# lippa.net
KiCad netlist of a schematic drawn in EAGLE
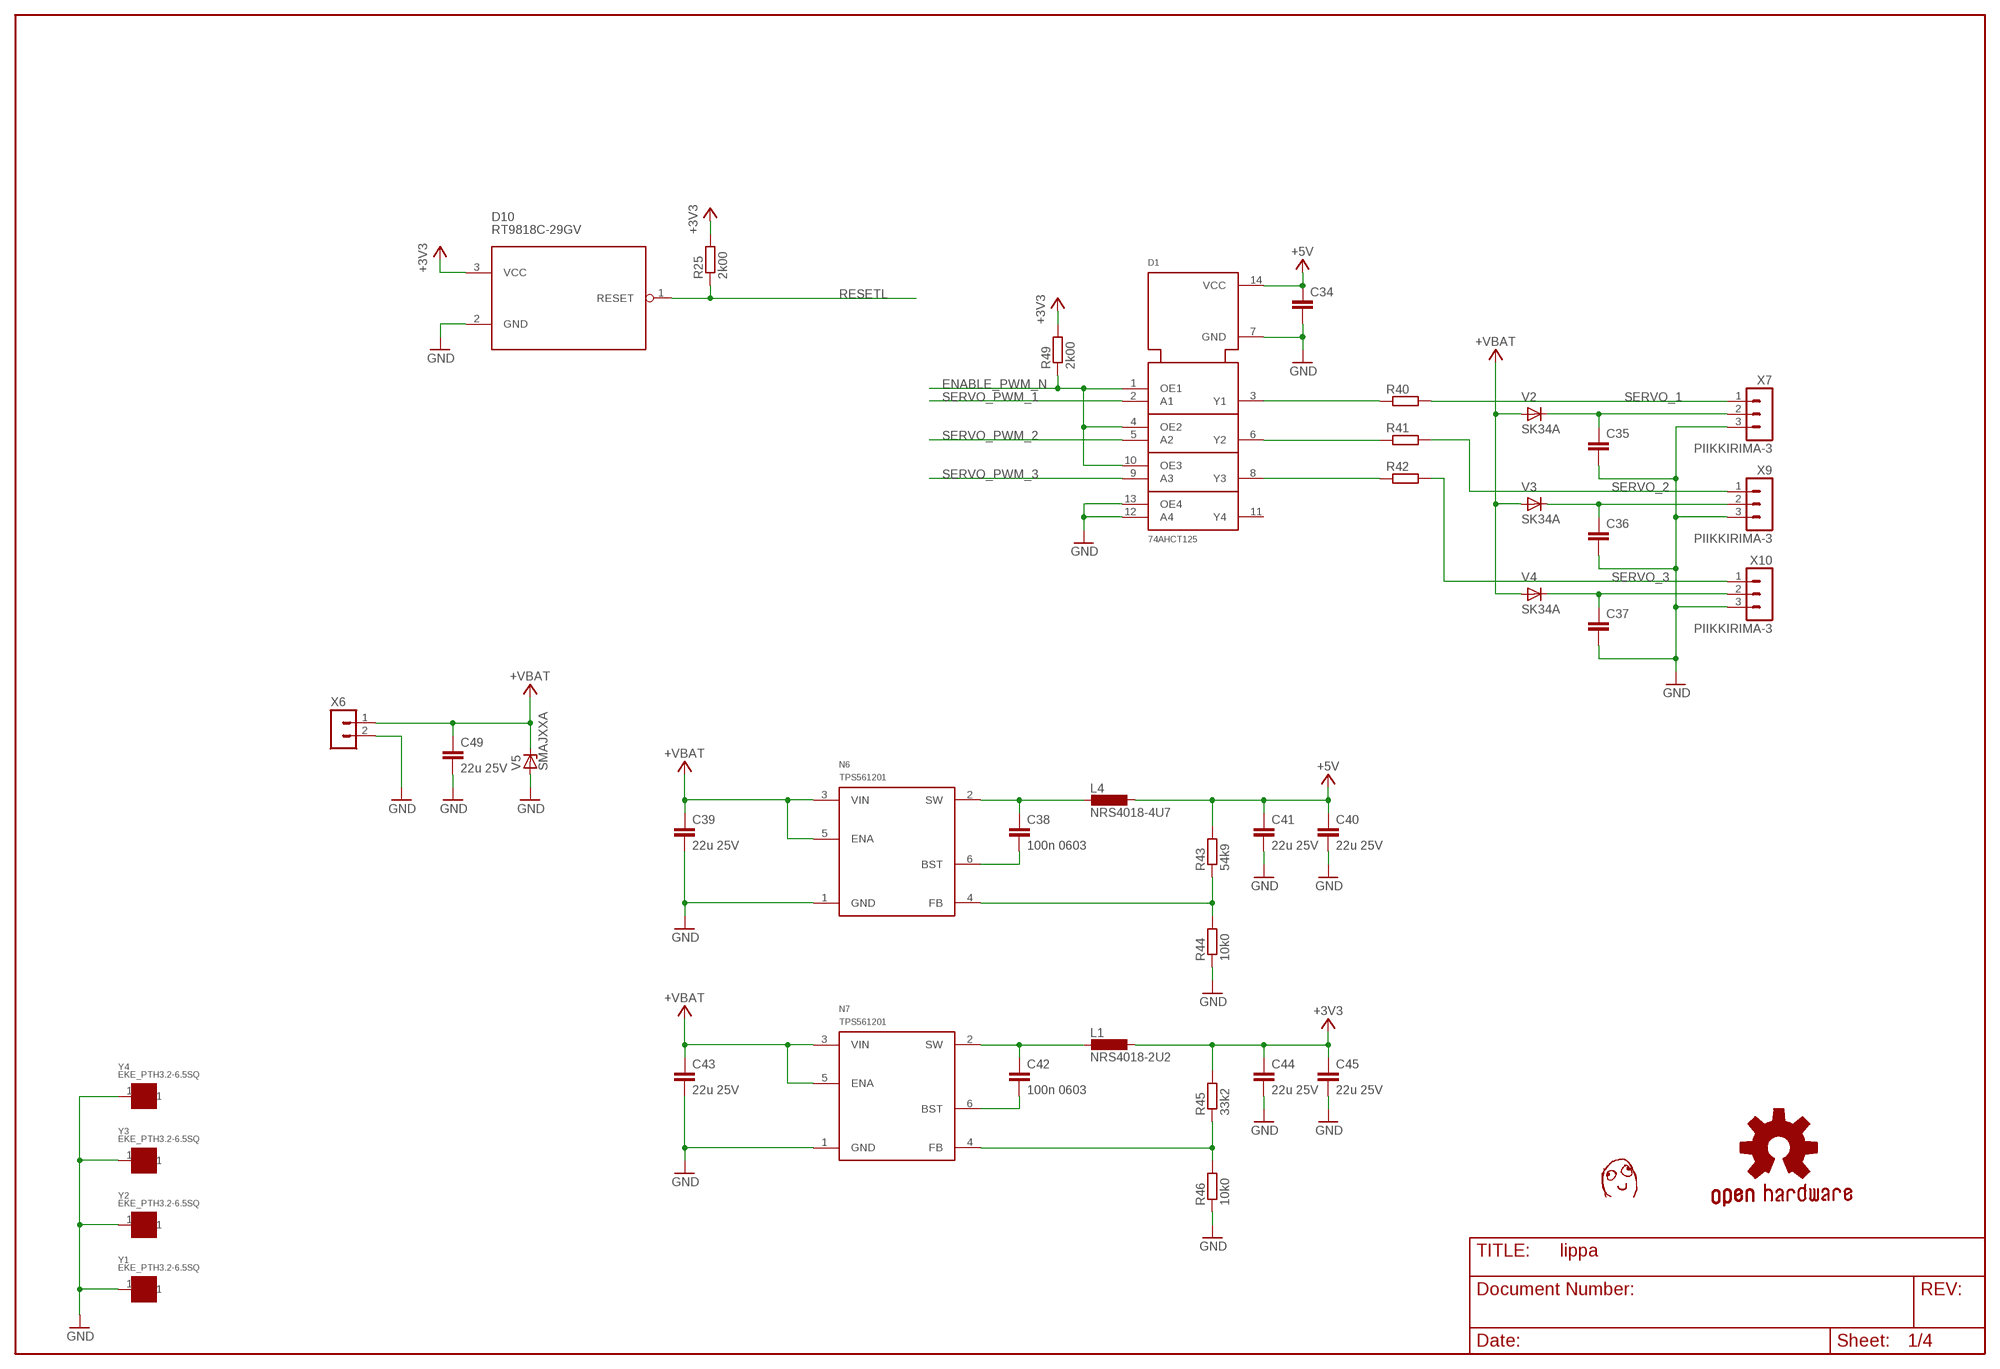
[diagram p0: schematic, sheet 1]
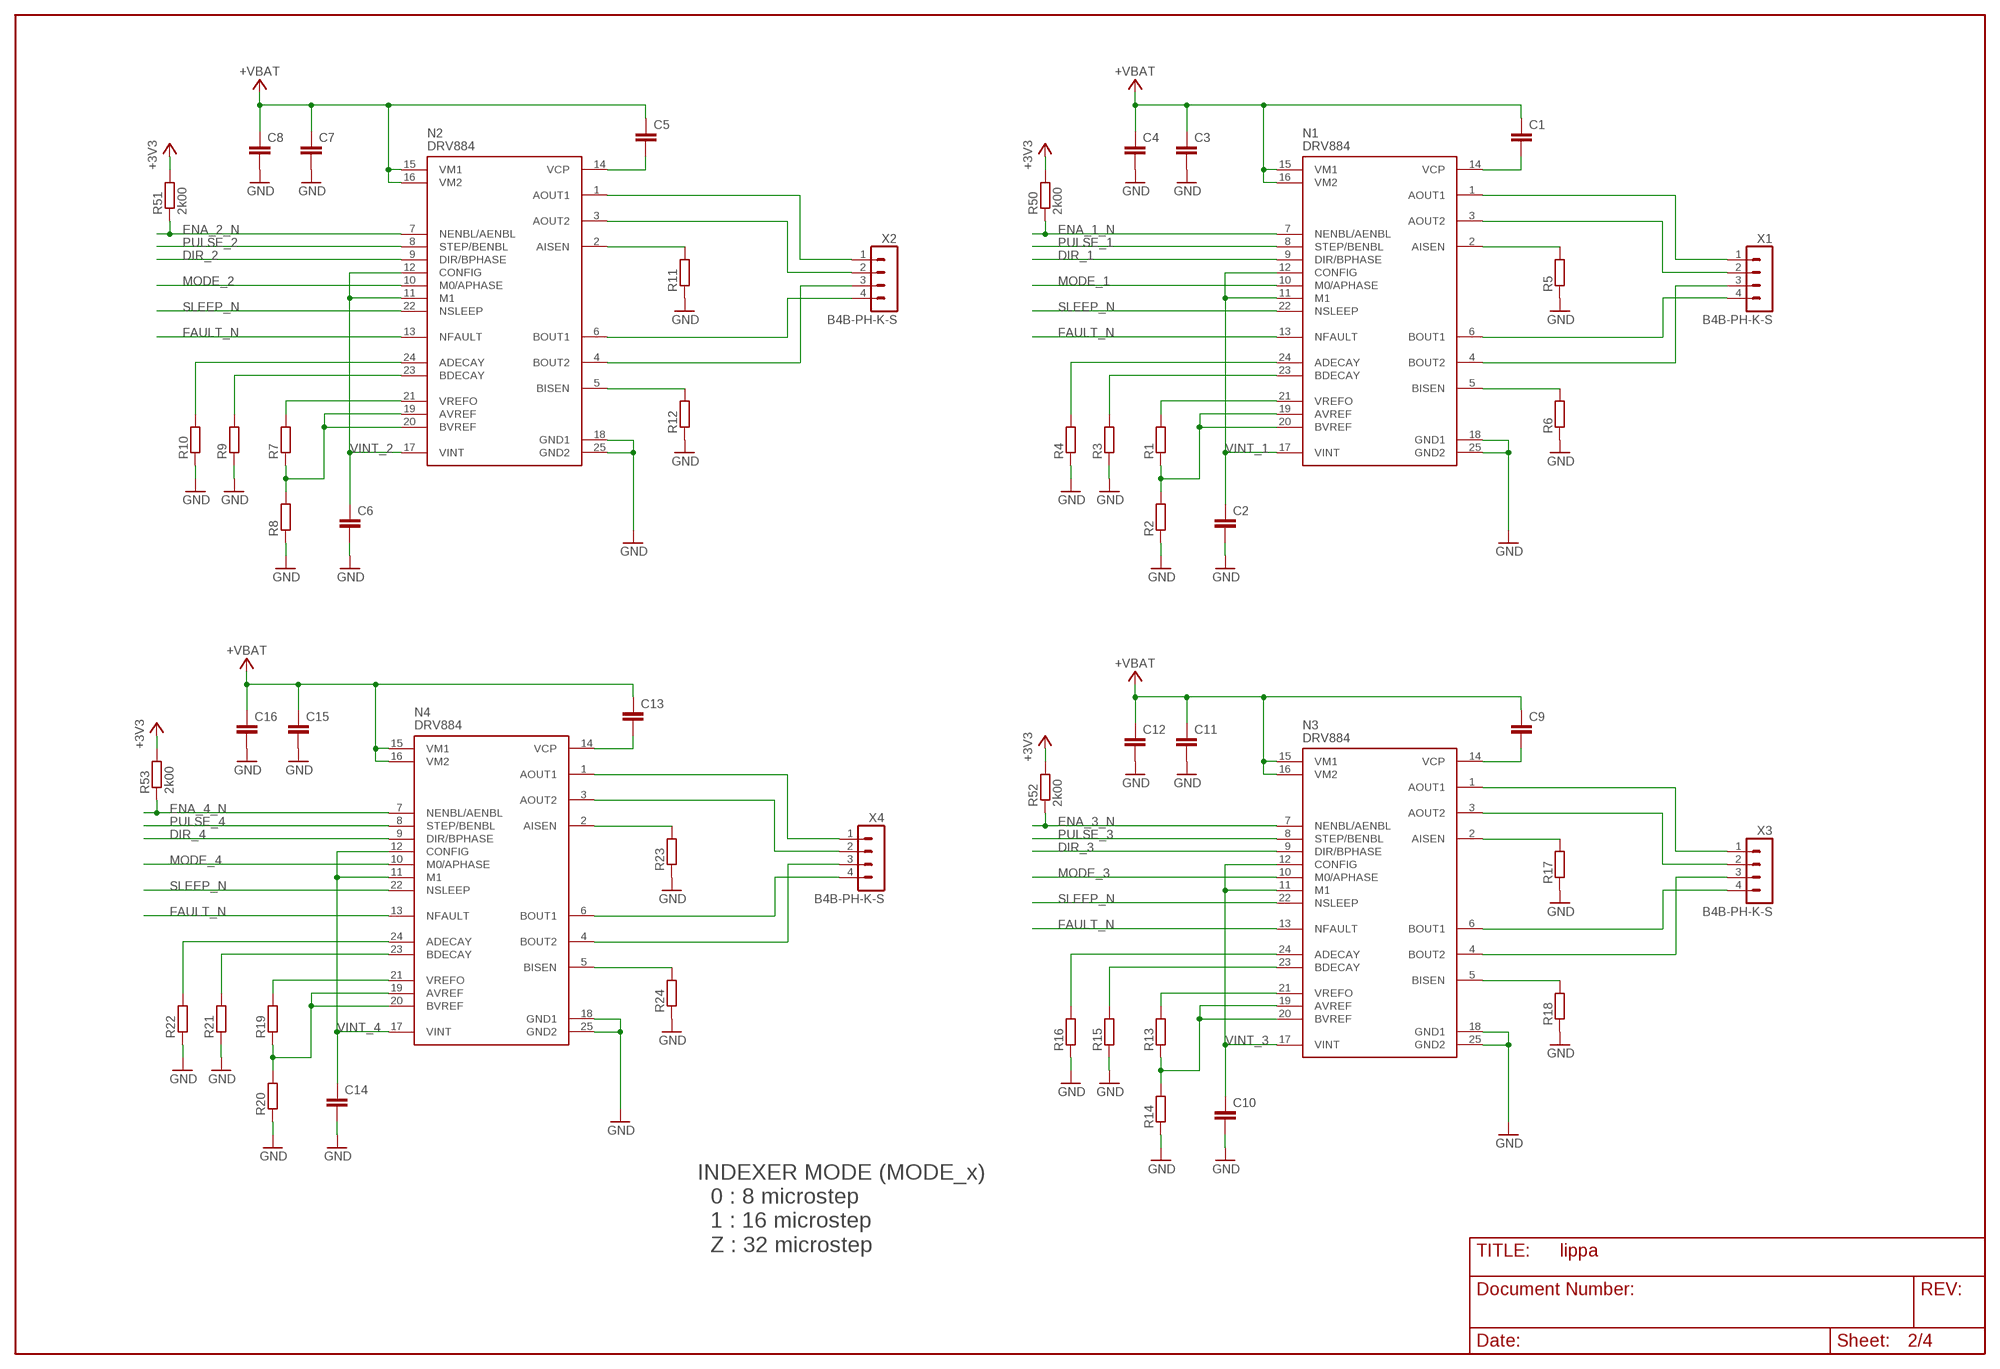
[diagram p1: schematic, sheet 2]
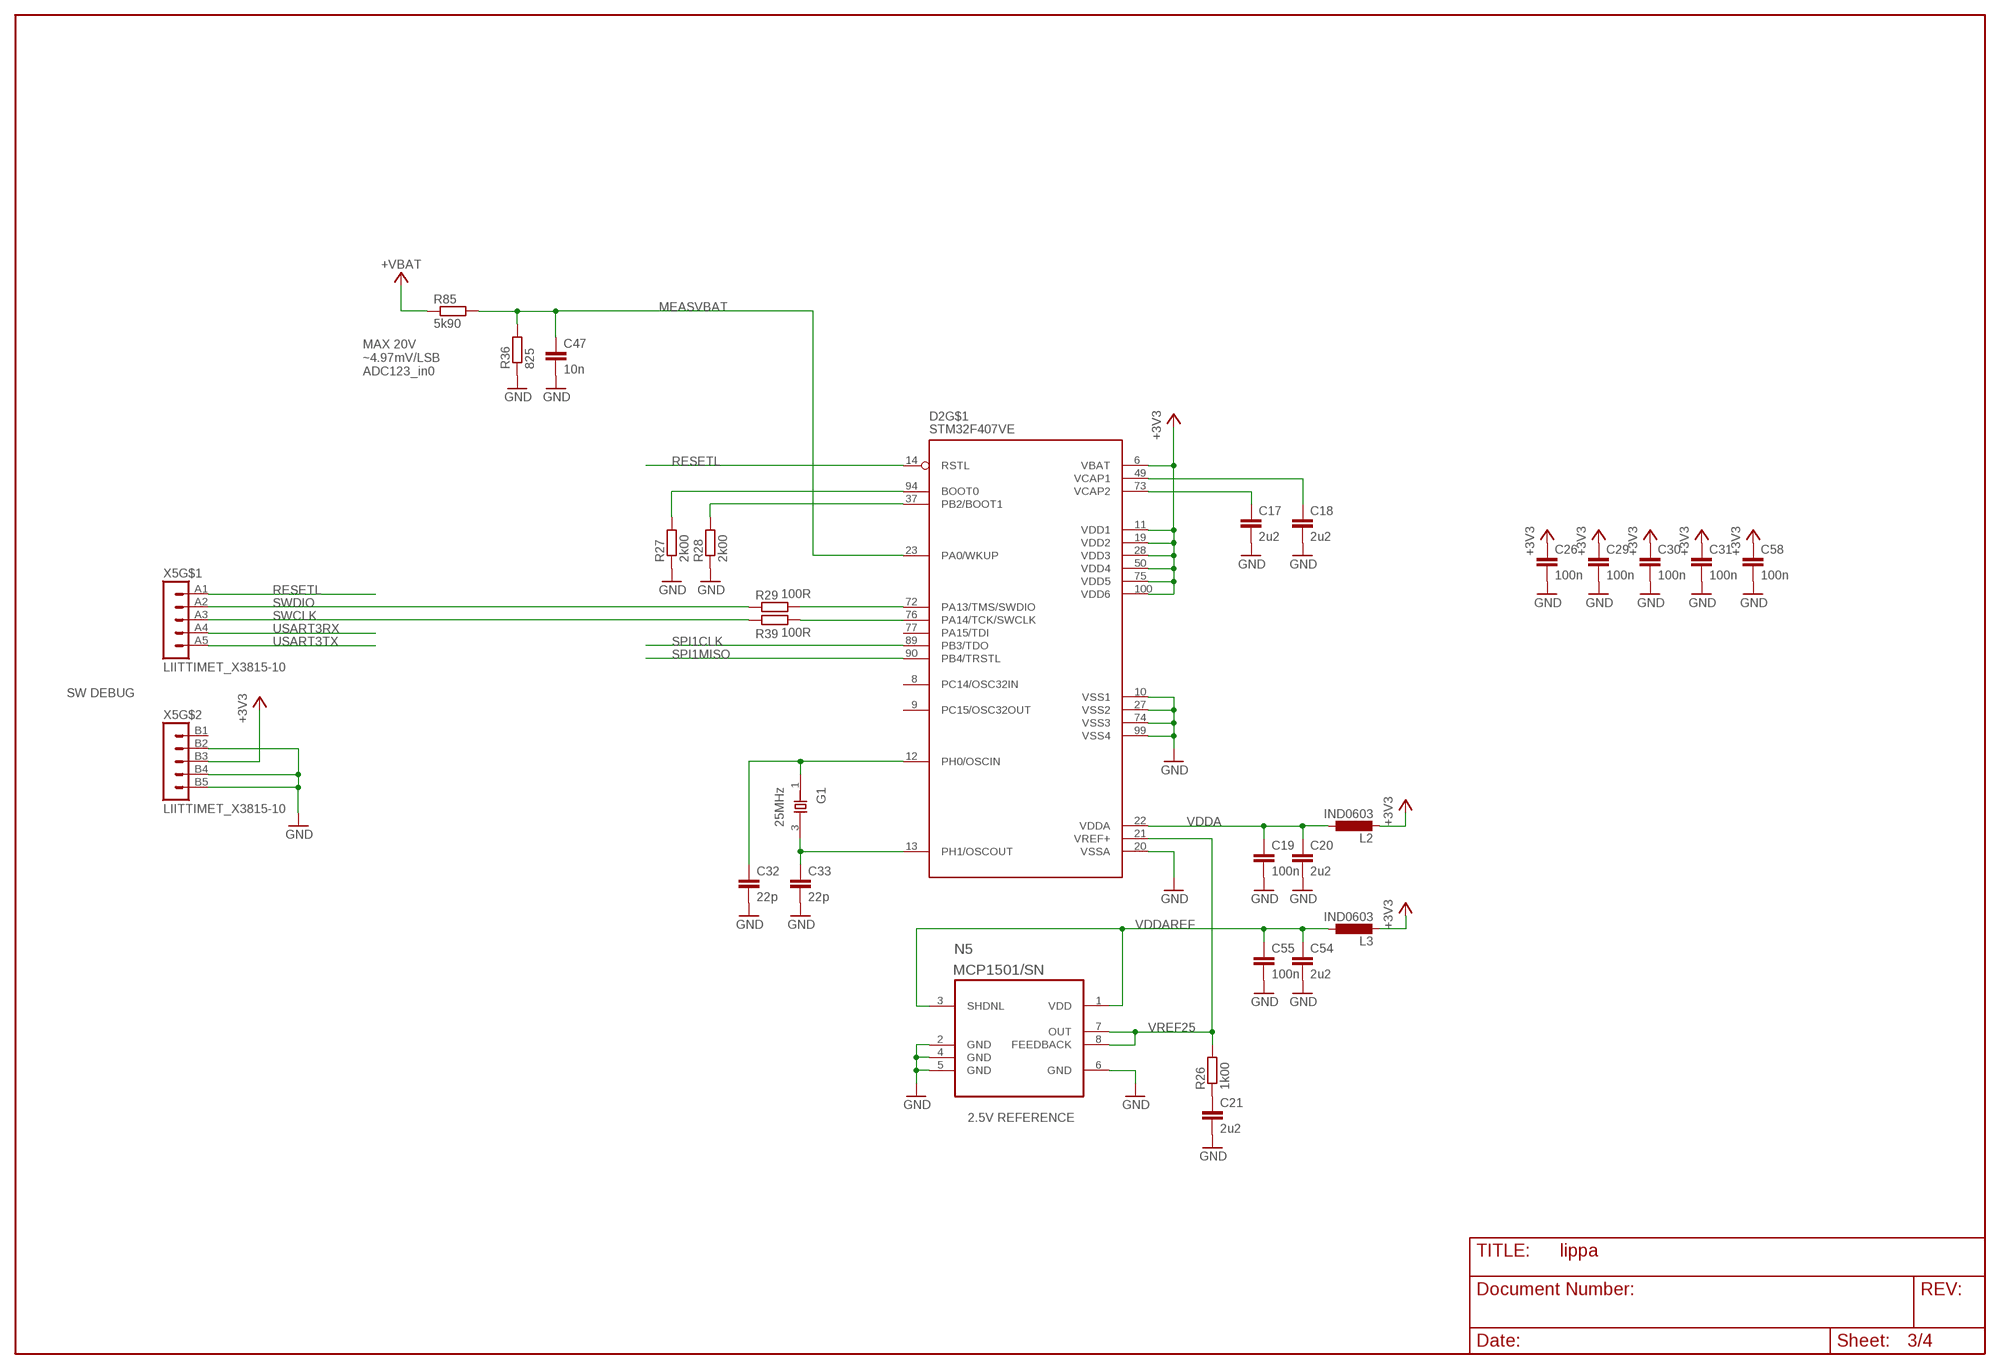
[diagram p2: schematic, sheet 3]
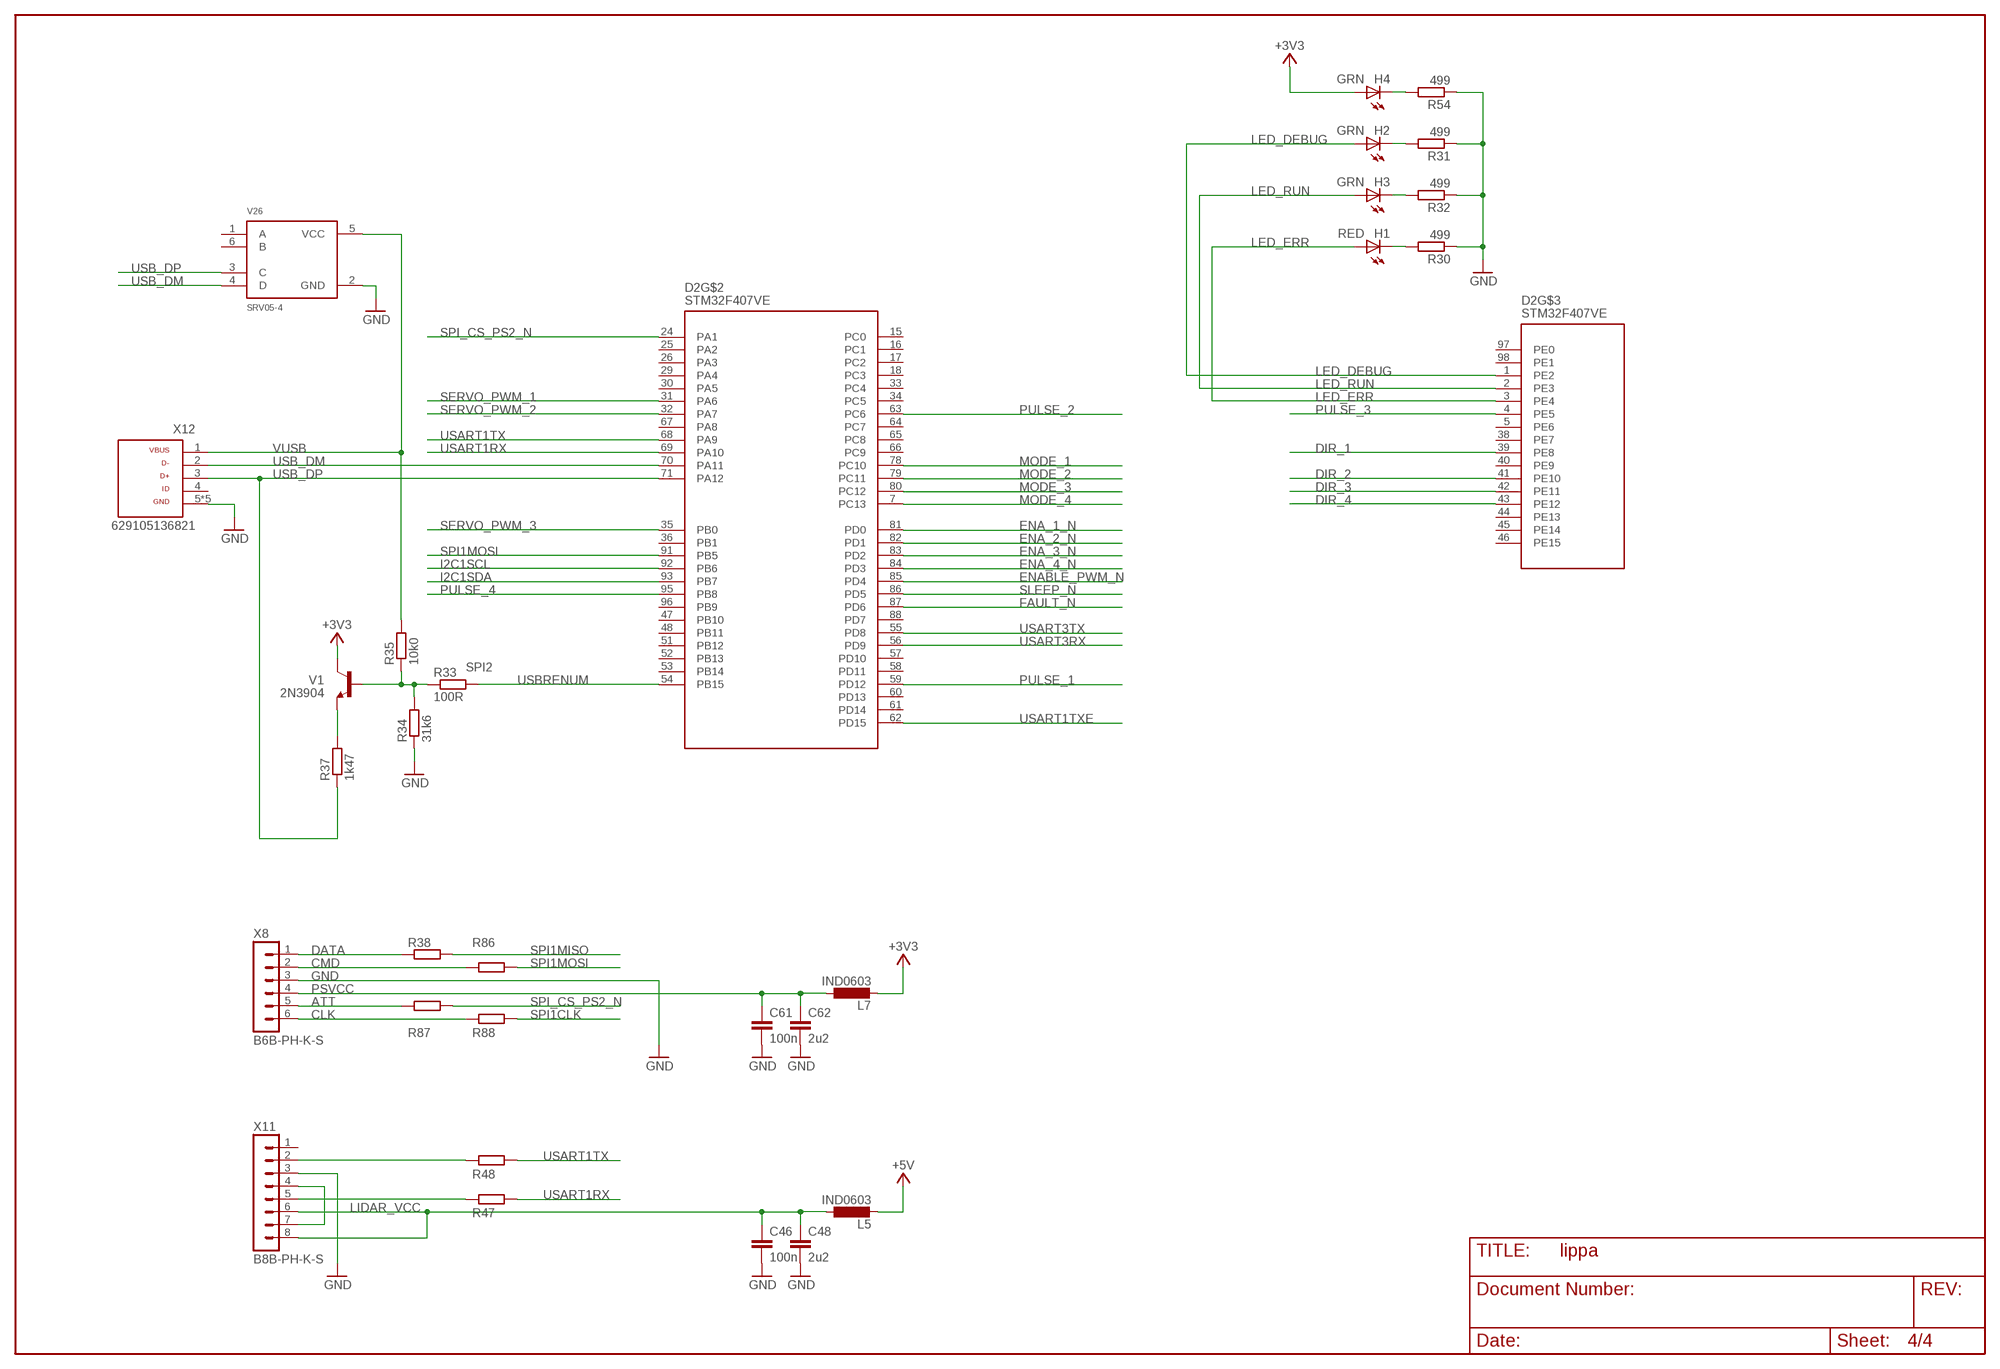
[diagram p3: schematic, sheet 4]

(export (version "E")
  (design (tool "Eeschema 10.0.6"))
  (components
    (comp (ref "C1")
      (value "OMAT_IC_2_CAP0603")
      (footprint "eagle-import:OMAT_IC_2_C0603")
      (libsource (lib "eagle-import") (part "OMAT_IC_2_CAP0603"))
    )
    (comp (ref "C2")
      (value "OMAT_IC_2_CAP0603")
      (footprint "eagle-import:OMAT_IC_2_C0603")
      (libsource (lib "eagle-import") (part "OMAT_IC_2_CAP0603"))
    )
    (comp (ref "C3")
      (value "OMAT_IC_2_CAP0603")
      (footprint "eagle-import:OMAT_IC_2_C0603")
      (libsource (lib "eagle-import") (part "OMAT_IC_2_CAP0603"))
    )
    (comp (ref "C4")
      (value "OMAT_IC_2_CAP0805")
      (footprint "eagle-import:OMAT_IC_2_C0805")
      (libsource (lib "eagle-import") (part "OMAT_IC_2_CAP0805"))
    )
    (comp (ref "C5")
      (value "OMAT_IC_2_CAP0603")
      (footprint "eagle-import:OMAT_IC_2_C0603")
      (libsource (lib "eagle-import") (part "OMAT_IC_2_CAP0603"))
    )
    (comp (ref "C6")
      (value "OMAT_IC_2_CAP0603")
      (footprint "eagle-import:OMAT_IC_2_C0603")
      (libsource (lib "eagle-import") (part "OMAT_IC_2_CAP0603"))
    )
    (comp (ref "C7")
      (value "OMAT_IC_2_CAP0603")
      (footprint "eagle-import:OMAT_IC_2_C0603")
      (libsource (lib "eagle-import") (part "OMAT_IC_2_CAP0603"))
    )
    (comp (ref "C8")
      (value "OMAT_IC_2_CAP0805")
      (footprint "eagle-import:OMAT_IC_2_C0805")
      (libsource (lib "eagle-import") (part "OMAT_IC_2_CAP0805"))
    )
    (comp (ref "C9")
      (value "OMAT_IC_2_CAP0603")
      (footprint "eagle-import:OMAT_IC_2_C0603")
      (libsource (lib "eagle-import") (part "OMAT_IC_2_CAP0603"))
    )
    (comp (ref "C10")
      (value "OMAT_IC_2_CAP0603")
      (footprint "eagle-import:OMAT_IC_2_C0603")
      (libsource (lib "eagle-import") (part "OMAT_IC_2_CAP0603"))
    )
    (comp (ref "C11")
      (value "OMAT_IC_2_CAP0603")
      (footprint "eagle-import:OMAT_IC_2_C0603")
      (libsource (lib "eagle-import") (part "OMAT_IC_2_CAP0603"))
    )
    (comp (ref "C12")
      (value "OMAT_IC_2_CAP0805")
      (footprint "eagle-import:OMAT_IC_2_C0805")
      (libsource (lib "eagle-import") (part "OMAT_IC_2_CAP0805"))
    )
    (comp (ref "C13")
      (value "OMAT_IC_2_CAP0603")
      (footprint "eagle-import:OMAT_IC_2_C0603")
      (libsource (lib "eagle-import") (part "OMAT_IC_2_CAP0603"))
    )
    (comp (ref "C14")
      (value "OMAT_IC_2_CAP0603")
      (footprint "eagle-import:OMAT_IC_2_C0603")
      (libsource (lib "eagle-import") (part "OMAT_IC_2_CAP0603"))
    )
    (comp (ref "C15")
      (value "OMAT_IC_2_CAP0603")
      (footprint "eagle-import:OMAT_IC_2_C0603")
      (libsource (lib "eagle-import") (part "OMAT_IC_2_CAP0603"))
    )
    (comp (ref "C16")
      (value "OMAT_IC_2_CAP0805")
      (footprint "eagle-import:OMAT_IC_2_C0805")
      (libsource (lib "eagle-import") (part "OMAT_IC_2_CAP0805"))
    )
    (comp (ref "N1")
      (value "DRV884")
      (footprint "eagle-import:QFN50P400X400X100-25N")
      (libsource (lib "eagle-import") (part "DRV884"))
    )
    (comp (ref "N2")
      (value "DRV884")
      (footprint "eagle-import:QFN50P400X400X100-25N")
      (libsource (lib "eagle-import") (part "DRV884"))
    )
    (comp (ref "N3")
      (value "DRV884")
      (footprint "eagle-import:QFN50P400X400X100-25N")
      (libsource (lib "eagle-import") (part "DRV884"))
    )
    (comp (ref "N4")
      (value "DRV884")
      (footprint "eagle-import:QFN50P400X400X100-25N")
      (libsource (lib "eagle-import") (part "DRV884"))
    )
    (comp (ref "R1")
      (value "OMAT_IC_2_RES0603")
      (footprint "eagle-import:OMAT_IC_2_R0603")
      (libsource (lib "eagle-import") (part "OMAT_IC_2_RES0603"))
    )
    (comp (ref "R2")
      (value "OMAT_IC_2_RES0603")
      (footprint "eagle-import:OMAT_IC_2_R0603")
      (libsource (lib "eagle-import") (part "OMAT_IC_2_RES0603"))
    )
    (comp (ref "R3")
      (value "OMAT_IC_2_RES0603")
      (footprint "eagle-import:OMAT_IC_2_R0603")
      (libsource (lib "eagle-import") (part "OMAT_IC_2_RES0603"))
    )
    (comp (ref "R4")
      (value "OMAT_IC_2_RES0603")
      (footprint "eagle-import:OMAT_IC_2_R0603")
      (libsource (lib "eagle-import") (part "OMAT_IC_2_RES0603"))
    )
    (comp (ref "R5")
      (value "OMAT_IC_2_RES1206")
      (footprint "eagle-import:OMAT_IC_2_R1206")
      (libsource (lib "eagle-import") (part "OMAT_IC_2_RES1206"))
    )
    (comp (ref "R6")
      (value "OMAT_IC_2_RES1206")
      (footprint "eagle-import:OMAT_IC_2_R1206")
      (libsource (lib "eagle-import") (part "OMAT_IC_2_RES1206"))
    )
    (comp (ref "R7")
      (value "OMAT_IC_2_RES0603")
      (footprint "eagle-import:OMAT_IC_2_R0603")
      (libsource (lib "eagle-import") (part "OMAT_IC_2_RES0603"))
    )
    (comp (ref "R8")
      (value "OMAT_IC_2_RES0603")
      (footprint "eagle-import:OMAT_IC_2_R0603")
      (libsource (lib "eagle-import") (part "OMAT_IC_2_RES0603"))
    )
    (comp (ref "R9")
      (value "OMAT_IC_2_RES0603")
      (footprint "eagle-import:OMAT_IC_2_R0603")
      (libsource (lib "eagle-import") (part "OMAT_IC_2_RES0603"))
    )
    (comp (ref "R10")
      (value "OMAT_IC_2_RES0603")
      (footprint "eagle-import:OMAT_IC_2_R0603")
      (libsource (lib "eagle-import") (part "OMAT_IC_2_RES0603"))
    )
    (comp (ref "R11")
      (value "OMAT_IC_2_RES1206")
      (footprint "eagle-import:OMAT_IC_2_R1206")
      (libsource (lib "eagle-import") (part "OMAT_IC_2_RES1206"))
    )
    (comp (ref "R12")
      (value "OMAT_IC_2_RES1206")
      (footprint "eagle-import:OMAT_IC_2_R1206")
      (libsource (lib "eagle-import") (part "OMAT_IC_2_RES1206"))
    )
    (comp (ref "R13")
      (value "OMAT_IC_2_RES0603")
      (footprint "eagle-import:OMAT_IC_2_R0603")
      (libsource (lib "eagle-import") (part "OMAT_IC_2_RES0603"))
    )
    (comp (ref "R14")
      (value "OMAT_IC_2_RES0603")
      (footprint "eagle-import:OMAT_IC_2_R0603")
      (libsource (lib "eagle-import") (part "OMAT_IC_2_RES0603"))
    )
    (comp (ref "R15")
      (value "OMAT_IC_2_RES0603")
      (footprint "eagle-import:OMAT_IC_2_R0603")
      (libsource (lib "eagle-import") (part "OMAT_IC_2_RES0603"))
    )
    (comp (ref "R16")
      (value "OMAT_IC_2_RES0603")
      (footprint "eagle-import:OMAT_IC_2_R0603")
      (libsource (lib "eagle-import") (part "OMAT_IC_2_RES0603"))
    )
    (comp (ref "R17")
      (value "OMAT_IC_2_RES1206")
      (footprint "eagle-import:OMAT_IC_2_R1206")
      (libsource (lib "eagle-import") (part "OMAT_IC_2_RES1206"))
    )
    (comp (ref "R18")
      (value "OMAT_IC_2_RES1206")
      (footprint "eagle-import:OMAT_IC_2_R1206")
      (libsource (lib "eagle-import") (part "OMAT_IC_2_RES1206"))
    )
    (comp (ref "R19")
      (value "OMAT_IC_2_RES0603")
      (footprint "eagle-import:OMAT_IC_2_R0603")
      (libsource (lib "eagle-import") (part "OMAT_IC_2_RES0603"))
    )
    (comp (ref "R20")
      (value "OMAT_IC_2_RES0603")
      (footprint "eagle-import:OMAT_IC_2_R0603")
      (libsource (lib "eagle-import") (part "OMAT_IC_2_RES0603"))
    )
    (comp (ref "R21")
      (value "OMAT_IC_2_RES0603")
      (footprint "eagle-import:OMAT_IC_2_R0603")
      (libsource (lib "eagle-import") (part "OMAT_IC_2_RES0603"))
    )
    (comp (ref "R22")
      (value "OMAT_IC_2_RES0603")
      (footprint "eagle-import:OMAT_IC_2_R0603")
      (libsource (lib "eagle-import") (part "OMAT_IC_2_RES0603"))
    )
    (comp (ref "R23")
      (value "OMAT_IC_2_RES1206")
      (footprint "eagle-import:OMAT_IC_2_R1206")
      (libsource (lib "eagle-import") (part "OMAT_IC_2_RES1206"))
    )
    (comp (ref "R24")
      (value "OMAT_IC_2_RES1206")
      (footprint "eagle-import:OMAT_IC_2_R1206")
      (libsource (lib "eagle-import") (part "OMAT_IC_2_RES1206"))
    )
    (comp (ref "R50")
      (value "2k00")
      (footprint "eagle-import:R0603")
      (libsource (lib "eagle-import") (part "omat_ic_2_RES0603"))
    )
    (comp (ref "R51")
      (value "2k00")
      (footprint "eagle-import:R0603")
      (libsource (lib "eagle-import") (part "omat_ic_2_RES0603"))
    )
    (comp (ref "R52")
      (value "2k00")
      (footprint "eagle-import:R0603")
      (libsource (lib "eagle-import") (part "omat_ic_2_RES0603"))
    )
    (comp (ref "R53")
      (value "2k00")
      (footprint "eagle-import:R0603")
      (libsource (lib "eagle-import") (part "omat_ic_2_RES0603"))
    )
    (comp (ref "X1")
      (value "B4B-PH-K-S")
      (footprint "eagle-import:B4B-PH-K-S")
      (libsource (lib "eagle-import") (part "B4B-PH-K-S"))
    )
    (comp (ref "X2")
      (value "B4B-PH-K-S")
      (footprint "eagle-import:B4B-PH-K-S")
      (libsource (lib "eagle-import") (part "B4B-PH-K-S"))
    )
    (comp (ref "X3")
      (value "B4B-PH-K-S")
      (footprint "eagle-import:B4B-PH-K-S")
      (libsource (lib "eagle-import") (part "B4B-PH-K-S"))
    )
    (comp (ref "X4")
      (value "B4B-PH-K-S")
      (footprint "eagle-import:B4B-PH-K-S")
      (libsource (lib "eagle-import") (part "B4B-PH-K-S"))
    )
    (comp (ref "C34")
      (value "OMAT_IC_2_CAP0603")
      (footprint "eagle-import:OMAT_IC_2_C0603")
      (libsource (lib "eagle-import") (part "OMAT_IC_2_CAP0603"))
    )
    (comp (ref "C35")
      (value "OMAT_IC_2_CAP0603")
      (footprint "eagle-import:OMAT_IC_2_C0603")
      (libsource (lib "eagle-import") (part "OMAT_IC_2_CAP0603"))
    )
    (comp (ref "C36")
      (value "OMAT_IC_2_CAP0603")
      (footprint "eagle-import:OMAT_IC_2_C0603")
      (libsource (lib "eagle-import") (part "OMAT_IC_2_CAP0603"))
    )
    (comp (ref "C37")
      (value "OMAT_IC_2_CAP0603")
      (footprint "eagle-import:OMAT_IC_2_C0603")
      (libsource (lib "eagle-import") (part "OMAT_IC_2_CAP0603"))
    )
    (comp (ref "C38")
      (value "100n 0603")
      (footprint "eagle-import:OMAT_IC_2_C0603")
      (libsource (lib "eagle-import") (part "OMAT_IC_2_CAP0603"))
    )
    (comp (ref "C39")
      (value "22u 25V")
      (footprint "eagle-import:OMAT_IC_2_C0805")
      (libsource (lib "eagle-import") (part "OMAT_IC_2_CAP0805"))
    )
    (comp (ref "C40")
      (value "22u 25V")
      (footprint "eagle-import:OMAT_IC_2_C0805")
      (libsource (lib "eagle-import") (part "OMAT_IC_2_CAP0805"))
    )
    (comp (ref "C41")
      (value "22u 25V")
      (footprint "eagle-import:OMAT_IC_2_C0805")
      (libsource (lib "eagle-import") (part "OMAT_IC_2_CAP0805"))
    )
    (comp (ref "C42")
      (value "100n 0603")
      (footprint "eagle-import:OMAT_IC_2_C0603")
      (libsource (lib "eagle-import") (part "OMAT_IC_2_CAP0603"))
    )
    (comp (ref "C43")
      (value "22u 25V")
      (footprint "eagle-import:OMAT_IC_2_C0805")
      (libsource (lib "eagle-import") (part "OMAT_IC_2_CAP0805"))
    )
    (comp (ref "C44")
      (value "22u 25V")
      (footprint "eagle-import:OMAT_IC_2_C0805")
      (libsource (lib "eagle-import") (part "OMAT_IC_2_CAP0805"))
    )
    (comp (ref "C45")
      (value "22u 25V")
      (footprint "eagle-import:OMAT_IC_2_C0805")
      (libsource (lib "eagle-import") (part "OMAT_IC_2_CAP0805"))
    )
    (comp (ref "C49")
      (value "22u 25V")
      (footprint "eagle-import:OMAT_IC_2_C0805")
      (libsource (lib "eagle-import") (part "OMAT_IC_2_CAP0805"))
    )
    (comp (ref "D1")
      (value "74AHCT125")
      (footprint "eagle-import:SO14")
      (libsource (lib "eagle-import") (part "74AHCT125"))
    )
    (comp (ref "D10")
      (value "RT9818C-29GV")
      (footprint "eagle-import:SOT23")
      (libsource (lib "eagle-import") (part "RT9818C-29GV"))
    )
    (comp (ref "L1")
      (value "NRS4018-2U2")
      (footprint "eagle-import:NRS4018")
      (libsource (lib "eagle-import") (part "NRS4018-2U2"))
    )
    (comp (ref "L4")
      (value "NRS4018-4U7")
      (footprint "eagle-import:NRS4018")
      (libsource (lib "eagle-import") (part "NRS4018-4U7"))
    )
    (comp (ref "N6")
      (value "TPS561201")
      (footprint "eagle-import:OMAT_IC_2_SOT23-6")
      (libsource (lib "eagle-import") (part "TPS561201"))
    )
    (comp (ref "N7")
      (value "TPS561201")
      (footprint "eagle-import:OMAT_IC_2_SOT23-6")
      (libsource (lib "eagle-import") (part "TPS561201"))
    )
    (comp (ref "R25")
      (value "2k00")
      (footprint "eagle-import:R0603")
      (libsource (lib "eagle-import") (part "omat_ic_2_RES0603"))
    )
    (comp (ref "R40")
      (value "OMAT_IC_2_RES0603")
      (footprint "eagle-import:OMAT_IC_2_R0603")
      (libsource (lib "eagle-import") (part "OMAT_IC_2_RES0603"))
    )
    (comp (ref "R41")
      (value "OMAT_IC_2_RES0603")
      (footprint "eagle-import:OMAT_IC_2_R0603")
      (libsource (lib "eagle-import") (part "OMAT_IC_2_RES0603"))
    )
    (comp (ref "R42")
      (value "OMAT_IC_2_RES0603")
      (footprint "eagle-import:OMAT_IC_2_R0603")
      (libsource (lib "eagle-import") (part "OMAT_IC_2_RES0603"))
    )
    (comp (ref "R43")
      (value "54k9")
      (footprint "eagle-import:OMAT_IC_2_R0603")
      (libsource (lib "eagle-import") (part "OMAT_IC_2_RES0603"))
    )
    (comp (ref "R44")
      (value "10k0")
      (footprint "eagle-import:OMAT_IC_2_R0603")
      (libsource (lib "eagle-import") (part "OMAT_IC_2_RES0603"))
    )
    (comp (ref "R45")
      (value "33k2")
      (footprint "eagle-import:OMAT_IC_2_R0603")
      (libsource (lib "eagle-import") (part "OMAT_IC_2_RES0603"))
    )
    (comp (ref "R46")
      (value "10k0")
      (footprint "eagle-import:OMAT_IC_2_R0603")
      (libsource (lib "eagle-import") (part "OMAT_IC_2_RES0603"))
    )
    (comp (ref "R49")
      (value "2k00")
      (footprint "eagle-import:R0603")
      (libsource (lib "eagle-import") (part "omat_ic_2_RES0603"))
    )
    (comp (ref "U$1")
      (value "DAFUG")
      (footprint "eagle-import:DAFUG")
      (libsource (lib "eagle-import") (part "DAFUG"))
    )
    (comp (ref "V2")
      (value "SK34A")
      (footprint "eagle-import:OMAT_IC_2_DO214AC")
      (libsource (lib "eagle-import") (part "SK34A"))
    )
    (comp (ref "V3")
      (value "SK34A")
      (footprint "eagle-import:OMAT_IC_2_DO214AC")
      (libsource (lib "eagle-import") (part "SK34A"))
    )
    (comp (ref "V4")
      (value "SK34A")
      (footprint "eagle-import:OMAT_IC_2_DO214AC")
      (libsource (lib "eagle-import") (part "SK34A"))
    )
    (comp (ref "V5")
      (value "SMAJXXA")
      (footprint "eagle-import:DO214AC")
      (libsource (lib "eagle-import") (part "SMAJXXA"))
    )
    (comp (ref "X6")
      (value "TE_RUUVILIITIN2")
      (footprint "eagle-import:TE_RUUVILIITIN2")
      (libsource (lib "eagle-import") (part "TE_RUUVILIITIN2"))
    )
    (comp (ref "X7")
      (value "PIIKKIRIMA-3")
      (footprint "eagle-import:PIIKKIRIMA-3")
      (libsource (lib "eagle-import") (part "PIIKKIRIMA-3"))
    )
    (comp (ref "X9")
      (value "PIIKKIRIMA-3")
      (footprint "eagle-import:PIIKKIRIMA-3")
      (libsource (lib "eagle-import") (part "PIIKKIRIMA-3"))
    )
    (comp (ref "X10")
      (value "PIIKKIRIMA-3")
      (footprint "eagle-import:PIIKKIRIMA-3")
      (libsource (lib "eagle-import") (part "PIIKKIRIMA-3"))
    )
    (comp (ref "Y1")
      (value "EKE_PTH3.2-6.5SQ")
      (footprint "eagle-import:EKE_PTH-3.2-6.5SQ")
      (libsource (lib "eagle-import") (part "EKE_PTH3.2-6.5SQ"))
    )
    (comp (ref "Y2")
      (value "EKE_PTH3.2-6.5SQ")
      (footprint "eagle-import:EKE_PTH-3.2-6.5SQ")
      (libsource (lib "eagle-import") (part "EKE_PTH3.2-6.5SQ"))
    )
    (comp (ref "Y3")
      (value "EKE_PTH3.2-6.5SQ")
      (footprint "eagle-import:EKE_PTH-3.2-6.5SQ")
      (libsource (lib "eagle-import") (part "EKE_PTH3.2-6.5SQ"))
    )
    (comp (ref "Y4")
      (value "EKE_PTH3.2-6.5SQ")
      (footprint "eagle-import:EKE_PTH-3.2-6.5SQ")
      (libsource (lib "eagle-import") (part "EKE_PTH3.2-6.5SQ"))
    )
    (comp (ref "C46")
      (value "100n")
      (footprint "eagle-import:C0603")
      (libsource (lib "eagle-import") (part "CAP0603"))
    )
    (comp (ref "C48")
      (value "2u2")
      (footprint "eagle-import:C0603")
      (libsource (lib "eagle-import") (part "CAP0603"))
    )
    (comp (ref "C61")
      (value "100n")
      (footprint "eagle-import:C0603")
      (libsource (lib "eagle-import") (part "CAP0603"))
    )
    (comp (ref "C62")
      (value "2u2")
      (footprint "eagle-import:C0603")
      (libsource (lib "eagle-import") (part "CAP0603"))
    )
    (comp (ref "D2")
      (value "STM32F407VE")
      (footprint "eagle-import:LQFP-100")
      (libsource (lib "eagle-import") (part "STM32F407VE"))
    )
    (comp (ref "H1")
      (value "RED")
      (footprint "eagle-import:CHIP-LED0603")
      (libsource (lib "eagle-import") (part "LEDCHIP-LED0603"))
    )
    (comp (ref "H2")
      (value "GRN")
      (footprint "eagle-import:CHIP-LED0603")
      (libsource (lib "eagle-import") (part "LEDCHIP-LED0603"))
    )
    (comp (ref "H3")
      (value "GRN")
      (footprint "eagle-import:CHIP-LED0603")
      (libsource (lib "eagle-import") (part "LEDCHIP-LED0603"))
    )
    (comp (ref "H4")
      (value "GRN")
      (footprint "eagle-import:CHIP-LED0603")
      (libsource (lib "eagle-import") (part "LEDCHIP-LED0603"))
    )
    (comp (ref "L5")
      (value "IND0603")
      (footprint "eagle-import:R0603")
      (libsource (lib "eagle-import") (part "IND0603"))
    )
    (comp (ref "L7")
      (value "IND0603")
      (footprint "eagle-import:R0603")
      (libsource (lib "eagle-import") (part "IND0603"))
    )
    (comp (ref "R30")
      (value "499")
      (footprint "eagle-import:R0603")
      (libsource (lib "eagle-import") (part "omat_ic_2_RES0603"))
    )
    (comp (ref "R31")
      (value "499")
      (footprint "eagle-import:R0603")
      (libsource (lib "eagle-import") (part "omat_ic_2_RES0603"))
    )
    (comp (ref "R32")
      (value "499")
      (footprint "eagle-import:R0603")
      (libsource (lib "eagle-import") (part "omat_ic_2_RES0603"))
    )
    (comp (ref "R33")
      (value "100R")
      (footprint "eagle-import:PASSIIVIT_R0603")
      (libsource (lib "eagle-import") (part "PASSIIVIT_RES0603"))
    )
    (comp (ref "R34")
      (value "31k6")
      (footprint "eagle-import:PASSIIVIT_R0603")
      (libsource (lib "eagle-import") (part "PASSIIVIT_RES0603"))
    )
    (comp (ref "R35")
      (value "10k0")
      (footprint "eagle-import:PASSIIVIT_R0603")
      (libsource (lib "eagle-import") (part "PASSIIVIT_RES0603"))
    )
    (comp (ref "R37")
      (value "1k47")
      (footprint "eagle-import:PASSIIVIT_R0603")
      (libsource (lib "eagle-import") (part "PASSIIVIT_RES0603"))
    )
    (comp (ref "R38")
      (value "RES0603")
      (footprint "eagle-import:OMAT_IC_2_R0603")
      (libsource (lib "eagle-import") (part "RES0603"))
    )
    (comp (ref "R47")
      (value "RES0603")
      (footprint "eagle-import:OMAT_IC_2_R0603")
      (libsource (lib "eagle-import") (part "RES0603"))
    )
    (comp (ref "R48")
      (value "RES0603")
      (footprint "eagle-import:OMAT_IC_2_R0603")
      (libsource (lib "eagle-import") (part "RES0603"))
    )
    (comp (ref "R54")
      (value "499")
      (footprint "eagle-import:R0603")
      (libsource (lib "eagle-import") (part "omat_ic_2_RES0603"))
    )
    (comp (ref "R86")
      (value "RES0603")
      (footprint "eagle-import:OMAT_IC_2_R0603")
      (libsource (lib "eagle-import") (part "RES0603"))
    )
    (comp (ref "R87")
      (value "RES0603")
      (footprint "eagle-import:OMAT_IC_2_R0603")
      (libsource (lib "eagle-import") (part "RES0603"))
    )
    (comp (ref "R88")
      (value "RES0603")
      (footprint "eagle-import:OMAT_IC_2_R0603")
      (libsource (lib "eagle-import") (part "RES0603"))
    )
    (comp (ref "V1")
      (value "2N3904")
      (footprint "eagle-import:OMAT_IC_2_SOT23")
      (libsource (lib "eagle-import") (part "2N3904"))
    )
    (comp (ref "V26")
      (value "SRV05-4")
      (footprint "eagle-import:OMAT_IC_2_SOT23-6")
      (libsource (lib "eagle-import") (part "SRV05-4"))
    )
    (comp (ref "X8")
      (value "B6B-PH-K-S")
      (footprint "eagle-import:B6B-PH-K-S")
      (libsource (lib "eagle-import") (part "B6B-PH-K-S"))
    )
    (comp (ref "X11")
      (value "B8B-PH-K-S")
      (footprint "eagle-import:B8B-PH-K-S")
      (libsource (lib "eagle-import") (part "B8B-PH-K-S"))
    )
    (comp (ref "X12")
      (value "629105136821")
      (footprint "eagle-import:629105136821")
      (libsource (lib "eagle-import") (part "629105136821"))
    )
    (comp (ref "C17")
      (value "2u2")
      (footprint "eagle-import:C0603")
      (libsource (lib "eagle-import") (part "CAP0603"))
    )
    (comp (ref "C18")
      (value "2u2")
      (footprint "eagle-import:C0603")
      (libsource (lib "eagle-import") (part "CAP0603"))
    )
    (comp (ref "C19")
      (value "100n")
      (footprint "eagle-import:C0603")
      (libsource (lib "eagle-import") (part "CAP0603"))
    )
    (comp (ref "C20")
      (value "2u2")
      (footprint "eagle-import:C0603")
      (libsource (lib "eagle-import") (part "CAP0603"))
    )
    (comp (ref "C21")
      (value "2u2")
      (footprint "eagle-import:C0603")
      (libsource (lib "eagle-import") (part "CAP0603"))
    )
    (comp (ref "C26")
      (value "100n")
      (footprint "eagle-import:C0603")
      (libsource (lib "eagle-import") (part "CAP0603"))
    )
    (comp (ref "C29")
      (value "100n")
      (footprint "eagle-import:C0603")
      (libsource (lib "eagle-import") (part "CAP0603"))
    )
    (comp (ref "C30")
      (value "100n")
      (footprint "eagle-import:C0603")
      (libsource (lib "eagle-import") (part "CAP0603"))
    )
    (comp (ref "C31")
      (value "100n")
      (footprint "eagle-import:C0603")
      (libsource (lib "eagle-import") (part "CAP0603"))
    )
    (comp (ref "C32")
      (value "22p")
      (footprint "eagle-import:C0603")
      (libsource (lib "eagle-import") (part "CAP0603"))
    )
    (comp (ref "C33")
      (value "22p")
      (footprint "eagle-import:C0603")
      (libsource (lib "eagle-import") (part "CAP0603"))
    )
    (comp (ref "C47")
      (value "10n")
      (footprint "eagle-import:C0603")
      (libsource (lib "eagle-import") (part "CAP0603"))
    )
    (comp (ref "C54")
      (value "2u2")
      (footprint "eagle-import:C0603")
      (libsource (lib "eagle-import") (part "CAP0603"))
    )
    (comp (ref "C55")
      (value "100n")
      (footprint "eagle-import:C0603")
      (libsource (lib "eagle-import") (part "CAP0603"))
    )
    (comp (ref "C58")
      (value "100n")
      (footprint "eagle-import:C0603")
      (libsource (lib "eagle-import") (part "CAP0603"))
    )
    (comp (ref "G1")
      (value "25MHz")
      (footprint "eagle-import:X_3225")
      (libsource (lib "eagle-import") (part "XTAL_3225_SMD"))
    )
    (comp (ref "L2")
      (value "IND0603")
      (footprint "eagle-import:R0603")
      (libsource (lib "eagle-import") (part "IND0603"))
    )
    (comp (ref "L3")
      (value "IND0603")
      (footprint "eagle-import:R0603")
      (libsource (lib "eagle-import") (part "IND0603"))
    )
    (comp (ref "N5")
      (value "MCP1501/SN")
      (footprint "eagle-import:SOIC8-N_MC")
      (libsource (lib "eagle-import") (part "MCP1501/SN"))
    )
    (comp (ref "R26")
      (value "1k00")
      (footprint "eagle-import:R0603")
      (libsource (lib "eagle-import") (part "omat_ic_2_RES0603"))
    )
    (comp (ref "R27")
      (value "2k00")
      (footprint "eagle-import:R0603")
      (libsource (lib "eagle-import") (part "omat_ic_2_RES0603"))
    )
    (comp (ref "R28")
      (value "2k00")
      (footprint "eagle-import:R0603")
      (libsource (lib "eagle-import") (part "omat_ic_2_RES0603"))
    )
    (comp (ref "R29")
      (value "100R")
      (footprint "eagle-import:PASSIIVIT_R0603")
      (libsource (lib "eagle-import") (part "PASSIIVIT_RES0603"))
    )
    (comp (ref "R36")
      (value "825")
      (footprint "eagle-import:R0603")
      (libsource (lib "eagle-import") (part "omat_ic_2_RES0603"))
    )
    (comp (ref "R39")
      (value "100R")
      (footprint "eagle-import:PASSIIVIT_R0603")
      (libsource (lib "eagle-import") (part "PASSIIVIT_RES0603"))
    )
    (comp (ref "R85")
      (value "5k90")
      (footprint "eagle-import:R0603")
      (libsource (lib "eagle-import") (part "omat_ic_2_RES0603"))
    )
    (comp (ref "X5")
      (value "LIITTIMET_X3815-10")
      (footprint "eagle-import:LIITTIMET_15110102601")
      (libsource (lib "eagle-import") (part "LIITTIMET_X3815-10"))
    )
  )
  (nets
    (net (code "1") (name "+3V3") (class "Default")
      (node (ref "C26") (pin "1") (pinfunction "1_1") (pintype "passive"))
      (node (ref "C29") (pin "1") (pinfunction "1_1") (pintype "passive"))
      (node (ref "C30") (pin "1") (pinfunction "1_1") (pintype "passive"))
      (node (ref "C31") (pin "1") (pinfunction "1_1") (pintype "passive"))
      (node (ref "C44") (pin "1") (pinfunction "1_1") (pintype "passive"))
      (node (ref "C45") (pin "1") (pinfunction "1_1") (pintype "passive"))
      (node (ref "C58") (pin "1") (pinfunction "1_1") (pintype "passive"))
      (node (ref "D10") (pin "3") (pinfunction "VCC_3") (pintype "bidirectional"))
      (node (ref "D2") (pin "100") (pinfunction "VDD6_100") (pintype "bidirectional"))
      (node (ref "D2") (pin "11") (pinfunction "VDD1_11") (pintype "bidirectional"))
      (node (ref "D2") (pin "19") (pinfunction "VDD2_19") (pintype "bidirectional"))
      (node (ref "D2") (pin "28") (pinfunction "VDD3_28") (pintype "bidirectional"))
      (node (ref "D2") (pin "50") (pinfunction "VDD4_50") (pintype "bidirectional"))
      (node (ref "D2") (pin "6") (pinfunction "VBAT_6") (pintype "bidirectional"))
      (node (ref "D2") (pin "75") (pinfunction "VDD5_75") (pintype "bidirectional"))
      (node (ref "H4") (pin "A") (pinfunction "A_A") (pintype "passive"))
      (node (ref "L1") (pin "1") (pinfunction "1_1") (pintype "passive"))
      (node (ref "L2") (pin "2") (pinfunction "2_2") (pintype "passive"))
      (node (ref "L3") (pin "2") (pinfunction "2_2") (pintype "passive"))
      (node (ref "L7") (pin "2") (pinfunction "2_2") (pintype "passive"))
      (node (ref "R25") (pin "2") (pinfunction "2_2") (pintype "passive"))
      (node (ref "R45") (pin "2") (pinfunction "2_2") (pintype "passive"))
      (node (ref "R49") (pin "2") (pinfunction "2_2") (pintype "passive"))
      (node (ref "R50") (pin "2") (pinfunction "2_2") (pintype "passive"))
      (node (ref "R51") (pin "2") (pinfunction "2_2") (pintype "passive"))
      (node (ref "R52") (pin "2") (pinfunction "2_2") (pintype "passive"))
      (node (ref "R53") (pin "2") (pinfunction "2_2") (pintype "passive"))
      (node (ref "V1") (pin "3") (pinfunction "C_3") (pintype "passive"))
      (node (ref "X5") (pin "B3") (pinfunction "3_B3") (pintype "passive"))
    )
    (net (code "2") (name "+5V") (class "Default")
      (node (ref "C34") (pin "1") (pinfunction "1_1") (pintype "passive"))
      (node (ref "C40") (pin "1") (pinfunction "1_1") (pintype "passive"))
      (node (ref "C41") (pin "1") (pinfunction "1_1") (pintype "passive"))
      (node (ref "D1") (pin "14") (pinfunction "VCC_14") (pintype "bidirectional"))
      (node (ref "L4") (pin "1") (pinfunction "1_1") (pintype "passive"))
      (node (ref "L5") (pin "2") (pinfunction "2_2") (pintype "passive"))
      (node (ref "R43") (pin "2") (pinfunction "2_2") (pintype "passive"))
    )
    (net (code "3") (name "+VBAT") (class "Default")
      (node (ref "C1") (pin "1") (pinfunction "1_1") (pintype "passive"))
      (node (ref "C11") (pin "1") (pinfunction "1_1") (pintype "passive"))
      (node (ref "C12") (pin "1") (pinfunction "1_1") (pintype "passive"))
      (node (ref "C13") (pin "1") (pinfunction "1_1") (pintype "passive"))
      (node (ref "C15") (pin "1") (pinfunction "1_1") (pintype "passive"))
      (node (ref "C16") (pin "1") (pinfunction "1_1") (pintype "passive"))
      (node (ref "C3") (pin "1") (pinfunction "1_1") (pintype "passive"))
      (node (ref "C39") (pin "1") (pinfunction "1_1") (pintype "passive"))
      (node (ref "C4") (pin "1") (pinfunction "1_1") (pintype "passive"))
      (node (ref "C43") (pin "1") (pinfunction "1_1") (pintype "passive"))
      (node (ref "C49") (pin "1") (pinfunction "1_1") (pintype "passive"))
      (node (ref "C5") (pin "1") (pinfunction "1_1") (pintype "passive"))
      (node (ref "C7") (pin "1") (pinfunction "1_1") (pintype "passive"))
      (node (ref "C8") (pin "1") (pinfunction "1_1") (pintype "passive"))
      (node (ref "C9") (pin "1") (pinfunction "1_1") (pintype "passive"))
      (node (ref "N1") (pin "15") (pinfunction "VM1_15") (pintype "bidirectional"))
      (node (ref "N1") (pin "16") (pinfunction "VM2_16") (pintype "bidirectional"))
      (node (ref "N2") (pin "15") (pinfunction "VM1_15") (pintype "bidirectional"))
      (node (ref "N2") (pin "16") (pinfunction "VM2_16") (pintype "bidirectional"))
      (node (ref "N3") (pin "15") (pinfunction "VM1_15") (pintype "bidirectional"))
      (node (ref "N3") (pin "16") (pinfunction "VM2_16") (pintype "bidirectional"))
      (node (ref "N4") (pin "15") (pinfunction "VM1_15") (pintype "bidirectional"))
      (node (ref "N4") (pin "16") (pinfunction "VM2_16") (pintype "bidirectional"))
      (node (ref "N6") (pin "3") (pinfunction "VIN_3") (pintype "bidirectional"))
      (node (ref "N6") (pin "5") (pinfunction "ENA_5") (pintype "bidirectional"))
      (node (ref "N7") (pin "3") (pinfunction "VIN_3") (pintype "bidirectional"))
      (node (ref "N7") (pin "5") (pinfunction "ENA_5") (pintype "bidirectional"))
      (node (ref "R85") (pin "1") (pinfunction "1_1") (pintype "passive"))
      (node (ref "V2") (pin "A") (pinfunction "A_A") (pintype "passive"))
      (node (ref "V3") (pin "A") (pinfunction "A_A") (pintype "passive"))
      (node (ref "V4") (pin "A") (pinfunction "A_A") (pintype "passive"))
      (node (ref "V5") (pin "C") (pinfunction "C_C") (pintype "passive"))
      (node (ref "X6") (pin "1") (pinfunction "1_1") (pintype "passive"))
    )
    (net (code "4") (name "ATT") (class "Default")
      (node (ref "R87") (pin "1") (pinfunction "1_1") (pintype "passive"))
      (node (ref "X8") (pin "5") (pinfunction "5_5") (pintype "passive"))
    )
    (net (code "5") (name "CLK") (class "Default")
      (node (ref "R88") (pin "1") (pinfunction "1_1") (pintype "passive"))
      (node (ref "X8") (pin "6") (pinfunction "6_6") (pintype "passive"))
    )
    (net (code "6") (name "CMD") (class "Default")
      (node (ref "R86") (pin "1") (pinfunction "1_1") (pintype "passive"))
      (node (ref "X8") (pin "2") (pinfunction "2_2") (pintype "passive"))
    )
    (net (code "7") (name "DATA") (class "Default")
      (node (ref "R38") (pin "1") (pinfunction "1_1") (pintype "passive"))
      (node (ref "X8") (pin "1") (pinfunction "1_1") (pintype "passive"))
    )
    (net (code "8") (name "DIR_1") (class "Default")
      (node (ref "D2") (pin "39") (pinfunction "PE8_39") (pintype "bidirectional"))
      (node (ref "N1") (pin "9") (pinfunction "DIR/BPHASE_9") (pintype "bidirectional"))
    )
    (net (code "9") (name "DIR_2") (class "Default")
      (node (ref "D2") (pin "41") (pinfunction "PE10_41") (pintype "bidirectional"))
      (node (ref "N2") (pin "9") (pinfunction "DIR/BPHASE_9") (pintype "bidirectional"))
    )
    (net (code "10") (name "DIR_3") (class "Default")
      (node (ref "D2") (pin "42") (pinfunction "PE11_42") (pintype "bidirectional"))
      (node (ref "N3") (pin "9") (pinfunction "DIR/BPHASE_9") (pintype "bidirectional"))
    )
    (net (code "11") (name "DIR_4") (class "Default")
      (node (ref "D2") (pin "43") (pinfunction "PE12_43") (pintype "bidirectional"))
      (node (ref "N4") (pin "9") (pinfunction "DIR/BPHASE_9") (pintype "bidirectional"))
    )
    (net (code "12") (name "ENABLE_PWM_N") (class "Default")
      (node (ref "D1") (pin "1") (pinfunction "OE1_1") (pintype "bidirectional"))
      (node (ref "D1") (pin "10") (pinfunction "OE3_10") (pintype "bidirectional"))
      (node (ref "D1") (pin "4") (pinfunction "OE2_4") (pintype "bidirectional"))
      (node (ref "D2") (pin "85") (pinfunction "PD4_85") (pintype "bidirectional"))
      (node (ref "R49") (pin "1") (pinfunction "1_1") (pintype "passive"))
    )
    (net (code "13") (name "ENA_1_N") (class "Default")
      (node (ref "D2") (pin "81") (pinfunction "PD0_81") (pintype "bidirectional"))
      (node (ref "N1") (pin "7") (pinfunction "NENBL/AENBL_7") (pintype "bidirectional"))
      (node (ref "R50") (pin "1") (pinfunction "1_1") (pintype "passive"))
    )
    (net (code "14") (name "ENA_2_N") (class "Default")
      (node (ref "D2") (pin "82") (pinfunction "PD1_82") (pintype "bidirectional"))
      (node (ref "N2") (pin "7") (pinfunction "NENBL/AENBL_7") (pintype "bidirectional"))
      (node (ref "R51") (pin "1") (pinfunction "1_1") (pintype "passive"))
    )
    (net (code "15") (name "ENA_3_N") (class "Default")
      (node (ref "D2") (pin "83") (pinfunction "PD2_83") (pintype "bidirectional"))
      (node (ref "N3") (pin "7") (pinfunction "NENBL/AENBL_7") (pintype "bidirectional"))
      (node (ref "R52") (pin "1") (pinfunction "1_1") (pintype "passive"))
    )
    (net (code "16") (name "ENA_4_N") (class "Default")
      (node (ref "D2") (pin "84") (pinfunction "PD3_84") (pintype "bidirectional"))
      (node (ref "N4") (pin "7") (pinfunction "NENBL/AENBL_7") (pintype "bidirectional"))
      (node (ref "R53") (pin "1") (pinfunction "1_1") (pintype "passive"))
    )
    (net (code "17") (name "FAULT_N") (class "Default")
      (node (ref "D2") (pin "87") (pinfunction "PD6_87") (pintype "bidirectional"))
      (node (ref "N1") (pin "13") (pinfunction "NFAULT_13") (pintype "bidirectional"))
      (node (ref "N2") (pin "13") (pinfunction "NFAULT_13") (pintype "bidirectional"))
      (node (ref "N3") (pin "13") (pinfunction "NFAULT_13") (pintype "bidirectional"))
      (node (ref "N4") (pin "13") (pinfunction "NFAULT_13") (pintype "bidirectional"))
    )
    (net (code "18") (name "GND") (class "Default")
      (node (ref "C10") (pin "2") (pinfunction "2_2") (pintype "passive"))
      (node (ref "C11") (pin "2") (pinfunction "2_2") (pintype "passive"))
      (node (ref "C12") (pin "2") (pinfunction "2_2") (pintype "passive"))
      (node (ref "C14") (pin "2") (pinfunction "2_2") (pintype "passive"))
      (node (ref "C15") (pin "2") (pinfunction "2_2") (pintype "passive"))
      (node (ref "C16") (pin "2") (pinfunction "2_2") (pintype "passive"))
      (node (ref "C17") (pin "2") (pinfunction "2_2") (pintype "passive"))
      (node (ref "C18") (pin "2") (pinfunction "2_2") (pintype "passive"))
      (node (ref "C19") (pin "2") (pinfunction "2_2") (pintype "passive"))
      (node (ref "C2") (pin "2") (pinfunction "2_2") (pintype "passive"))
      (node (ref "C20") (pin "2") (pinfunction "2_2") (pintype "passive"))
      (node (ref "C21") (pin "2") (pinfunction "2_2") (pintype "passive"))
      (node (ref "C26") (pin "2") (pinfunction "2_2") (pintype "passive"))
      (node (ref "C29") (pin "2") (pinfunction "2_2") (pintype "passive"))
      (node (ref "C3") (pin "2") (pinfunction "2_2") (pintype "passive"))
      (node (ref "C30") (pin "2") (pinfunction "2_2") (pintype "passive"))
      (node (ref "C31") (pin "2") (pinfunction "2_2") (pintype "passive"))
      (node (ref "C32") (pin "2") (pinfunction "2_2") (pintype "passive"))
      (node (ref "C33") (pin "2") (pinfunction "2_2") (pintype "passive"))
      (node (ref "C34") (pin "2") (pinfunction "2_2") (pintype "passive"))
      (node (ref "C35") (pin "2") (pinfunction "2_2") (pintype "passive"))
      (node (ref "C36") (pin "2") (pinfunction "2_2") (pintype "passive"))
      (node (ref "C37") (pin "2") (pinfunction "2_2") (pintype "passive"))
      (node (ref "C39") (pin "2") (pinfunction "2_2") (pintype "passive"))
      (node (ref "C4") (pin "2") (pinfunction "2_2") (pintype "passive"))
      (node (ref "C40") (pin "2") (pinfunction "2_2") (pintype "passive"))
      (node (ref "C41") (pin "2") (pinfunction "2_2") (pintype "passive"))
      (node (ref "C43") (pin "2") (pinfunction "2_2") (pintype "passive"))
      (node (ref "C44") (pin "2") (pinfunction "2_2") (pintype "passive"))
      (node (ref "C45") (pin "2") (pinfunction "2_2") (pintype "passive"))
      (node (ref "C46") (pin "2") (pinfunction "2_2") (pintype "passive"))
      (node (ref "C47") (pin "2") (pinfunction "2_2") (pintype "passive"))
      (node (ref "C48") (pin "2") (pinfunction "2_2") (pintype "passive"))
      (node (ref "C49") (pin "2") (pinfunction "2_2") (pintype "passive"))
      (node (ref "C54") (pin "2") (pinfunction "2_2") (pintype "passive"))
      (node (ref "C55") (pin "2") (pinfunction "2_2") (pintype "passive"))
      (node (ref "C58") (pin "2") (pinfunction "2_2") (pintype "passive"))
      (node (ref "C6") (pin "2") (pinfunction "2_2") (pintype "passive"))
      (node (ref "C61") (pin "2") (pinfunction "2_2") (pintype "passive"))
      (node (ref "C62") (pin "2") (pinfunction "2_2") (pintype "passive"))
      (node (ref "C7") (pin "2") (pinfunction "2_2") (pintype "passive"))
      (node (ref "C8") (pin "2") (pinfunction "2_2") (pintype "passive"))
      (node (ref "D1") (pin "12") (pinfunction "A4_12") (pintype "bidirectional"))
      (node (ref "D1") (pin "13") (pinfunction "OE4_13") (pintype "bidirectional"))
      (node (ref "D1") (pin "7") (pinfunction "GND_7") (pintype "bidirectional"))
      (node (ref "D10") (pin "2") (pinfunction "GND_2") (pintype "bidirectional"))
      (node (ref "D2") (pin "10") (pinfunction "VSS1_10") (pintype "bidirectional"))
      (node (ref "D2") (pin "20") (pinfunction "VSSA_20") (pintype "bidirectional"))
      (node (ref "D2") (pin "27") (pinfunction "VSS2_27") (pintype "bidirectional"))
      (node (ref "D2") (pin "74") (pinfunction "VSS3_74") (pintype "bidirectional"))
      (node (ref "D2") (pin "99") (pinfunction "VSS4_99") (pintype "bidirectional"))
      (node (ref "N1") (pin "18") (pinfunction "GND1_18") (pintype "bidirectional"))
      (node (ref "N1") (pin "25") (pinfunction "GND2_25") (pintype "bidirectional"))
      (node (ref "N2") (pin "18") (pinfunction "GND1_18") (pintype "bidirectional"))
      (node (ref "N2") (pin "25") (pinfunction "GND2_25") (pintype "bidirectional"))
      (node (ref "N3") (pin "18") (pinfunction "GND1_18") (pintype "bidirectional"))
      (node (ref "N3") (pin "25") (pinfunction "GND2_25") (pintype "bidirectional"))
      (node (ref "N4") (pin "18") (pinfunction "GND1_18") (pintype "bidirectional"))
      (node (ref "N4") (pin "25") (pinfunction "GND2_25") (pintype "bidirectional"))
      (node (ref "N5") (pin "2") (pinfunction "GND_2") (pintype "bidirectional"))
      (node (ref "N5") (pin "4") (pinfunction "GND_4") (pintype "bidirectional"))
      (node (ref "N5") (pin "5") (pinfunction "GND_5") (pintype "bidirectional"))
      (node (ref "N5") (pin "6") (pinfunction "GND_6") (pintype "input"))
      (node (ref "N6") (pin "1") (pinfunction "GND_1") (pintype "bidirectional"))
      (node (ref "N7") (pin "1") (pinfunction "GND_1") (pintype "bidirectional"))
      (node (ref "R10") (pin "1") (pinfunction "1_1") (pintype "passive"))
      (node (ref "R11") (pin "1") (pinfunction "1_1") (pintype "passive"))
      (node (ref "R12") (pin "1") (pinfunction "1_1") (pintype "passive"))
      (node (ref "R14") (pin "1") (pinfunction "1_1") (pintype "passive"))
      (node (ref "R15") (pin "1") (pinfunction "1_1") (pintype "passive"))
      (node (ref "R16") (pin "1") (pinfunction "1_1") (pintype "passive"))
      (node (ref "R17") (pin "1") (pinfunction "1_1") (pintype "passive"))
      (node (ref "R18") (pin "1") (pinfunction "1_1") (pintype "passive"))
      (node (ref "R2") (pin "1") (pinfunction "1_1") (pintype "passive"))
      (node (ref "R20") (pin "1") (pinfunction "1_1") (pintype "passive"))
      (node (ref "R21") (pin "1") (pinfunction "1_1") (pintype "passive"))
      (node (ref "R22") (pin "1") (pinfunction "1_1") (pintype "passive"))
      (node (ref "R23") (pin "1") (pinfunction "1_1") (pintype "passive"))
      (node (ref "R24") (pin "1") (pinfunction "1_1") (pintype "passive"))
      (node (ref "R27") (pin "1") (pinfunction "1_1") (pintype "passive"))
      (node (ref "R28") (pin "1") (pinfunction "1_1") (pintype "passive"))
      (node (ref "R3") (pin "1") (pinfunction "1_1") (pintype "passive"))
      (node (ref "R30") (pin "1") (pinfunction "1_1") (pintype "passive"))
      (node (ref "R31") (pin "1") (pinfunction "1_1") (pintype "passive"))
      (node (ref "R32") (pin "1") (pinfunction "1_1") (pintype "passive"))
      (node (ref "R34") (pin "1") (pinfunction "1_1") (pintype "passive"))
      (node (ref "R36") (pin "1") (pinfunction "1_1") (pintype "passive"))
      (node (ref "R4") (pin "1") (pinfunction "1_1") (pintype "passive"))
      (node (ref "R44") (pin "1") (pinfunction "1_1") (pintype "passive"))
      (node (ref "R46") (pin "1") (pinfunction "1_1") (pintype "passive"))
      (node (ref "R5") (pin "1") (pinfunction "1_1") (pintype "passive"))
      (node (ref "R54") (pin "1") (pinfunction "1_1") (pintype "passive"))
      (node (ref "R6") (pin "1") (pinfunction "1_1") (pintype "passive"))
      (node (ref "R8") (pin "1") (pinfunction "1_1") (pintype "passive"))
      (node (ref "R9") (pin "1") (pinfunction "1_1") (pintype "passive"))
      (node (ref "V26") (pin "2") (pinfunction "GND_2") (pintype "bidirectional"))
      (node (ref "V5") (pin "A") (pinfunction "A_A") (pintype "passive"))
      (node (ref "X10") (pin "3") (pinfunction "3_3") (pintype "passive"))
      (node (ref "X11") (pin "3") (pinfunction "3_3") (pintype "passive"))
      (node (ref "X12") (pin "5") (pinfunction "5_5") (pintype "passive"))
      (node (ref "X12") (pin "Z1") (pinfunction "5_Z1") (pintype "passive"))
      (node (ref "X12") (pin "Z2") (pinfunction "5_Z2") (pintype "passive"))
      (node (ref "X12") (pin "Z3") (pinfunction "5_Z3") (pintype "passive"))
      (node (ref "X12") (pin "Z4") (pinfunction "5_Z4") (pintype "passive"))
      (node (ref "X5") (pin "B2") (pinfunction "2_B2") (pintype "passive"))
      (node (ref "X5") (pin "B4") (pinfunction "4_B4") (pintype "passive"))
      (node (ref "X5") (pin "B5") (pinfunction "5_B5") (pintype "passive"))
      (node (ref "X6") (pin "2") (pinfunction "2_2") (pintype "passive"))
      (node (ref "X7") (pin "3") (pinfunction "3_3") (pintype "passive"))
      (node (ref "X8") (pin "3") (pinfunction "3_3") (pintype "passive"))
      (node (ref "X9") (pin "3") (pinfunction "3_3") (pintype "passive"))
      (node (ref "Y1") (pin "1") (pinfunction "1_1") (pintype "bidirectional"))
      (node (ref "Y2") (pin "1") (pinfunction "1_1") (pintype "bidirectional"))
      (node (ref "Y3") (pin "1") (pinfunction "1_1") (pintype "bidirectional"))
      (node (ref "Y4") (pin "1") (pinfunction "1_1") (pintype "bidirectional"))
    )
    (net (code "19") (name "I2C1SCL") (class "Default")
      (node (ref "D2") (pin "92") (pinfunction "PB6_92") (pintype "bidirectional"))
    )
    (net (code "20") (name "I2C1SDA") (class "Default")
      (node (ref "D2") (pin "93") (pinfunction "PB7_93") (pintype "bidirectional"))
    )
    (net (code "21") (name "LED_DEBUG") (class "Default")
      (node (ref "D2") (pin "1") (pinfunction "PE2_1") (pintype "bidirectional"))
      (node (ref "H2") (pin "A") (pinfunction "A_A") (pintype "passive"))
    )
    (net (code "22") (name "LED_ERR") (class "Default")
      (node (ref "D2") (pin "3") (pinfunction "PE4_3") (pintype "bidirectional"))
      (node (ref "H1") (pin "A") (pinfunction "A_A") (pintype "passive"))
    )
    (net (code "23") (name "LED_RUN") (class "Default")
      (node (ref "D2") (pin "2") (pinfunction "PE3_2") (pintype "bidirectional"))
      (node (ref "H3") (pin "A") (pinfunction "A_A") (pintype "passive"))
    )
    (net (code "24") (name "LIDAR_VCC") (class "Default")
      (node (ref "C46") (pin "1") (pinfunction "1_1") (pintype "passive"))
      (node (ref "C48") (pin "1") (pinfunction "1_1") (pintype "passive"))
      (node (ref "L5") (pin "1") (pinfunction "1_1") (pintype "passive"))
      (node (ref "X11") (pin "6") (pinfunction "6_6") (pintype "passive"))
      (node (ref "X11") (pin "8") (pinfunction "8_8") (pintype "passive"))
    )
    (net (code "25") (name "MEASVBAT") (class "Default")
      (node (ref "C47") (pin "1") (pinfunction "1_1") (pintype "passive"))
      (node (ref "D2") (pin "23") (pinfunction "PA0/WKUP_23") (pintype "bidirectional"))
      (node (ref "R36") (pin "2") (pinfunction "2_2") (pintype "passive"))
      (node (ref "R85") (pin "2") (pinfunction "2_2") (pintype "passive"))
    )
    (net (code "26") (name "MODE_1") (class "Default")
      (node (ref "D2") (pin "78") (pinfunction "PC10_78") (pintype "bidirectional"))
      (node (ref "N1") (pin "10") (pinfunction "M0/APHASE_10") (pintype "bidirectional"))
    )
    (net (code "27") (name "MODE_2") (class "Default")
      (node (ref "D2") (pin "79") (pinfunction "PC11_79") (pintype "bidirectional"))
      (node (ref "N2") (pin "10") (pinfunction "M0/APHASE_10") (pintype "bidirectional"))
    )
    (net (code "28") (name "MODE_3") (class "Default")
      (node (ref "D2") (pin "80") (pinfunction "PC12_80") (pintype "bidirectional"))
      (node (ref "N3") (pin "10") (pinfunction "M0/APHASE_10") (pintype "bidirectional"))
    )
    (net (code "29") (name "MODE_4") (class "Default")
      (node (ref "D2") (pin "7") (pinfunction "PC13_7") (pintype "bidirectional"))
      (node (ref "N4") (pin "10") (pinfunction "M0/APHASE_10") (pintype "bidirectional"))
    )
    (net (code "30") (name "Net-(C21-Pad1)") (class "Default")
      (node (ref "C21") (pin "1") (pinfunction "1_1") (pintype "passive"))
      (node (ref "R26") (pin "1") (pinfunction "1_1") (pintype "passive"))
    )
    (net (code "31") (name "Net-(C35-Pad1)") (class "Default")
      (node (ref "C35") (pin "1") (pinfunction "1_1") (pintype "passive"))
      (node (ref "V2") (pin "C") (pinfunction "C_C") (pintype "passive"))
      (node (ref "X7") (pin "2") (pinfunction "2_2") (pintype "passive"))
    )
    (net (code "32") (name "Net-(C36-Pad1)") (class "Default")
      (node (ref "C36") (pin "1") (pinfunction "1_1") (pintype "passive"))
      (node (ref "V3") (pin "C") (pinfunction "C_C") (pintype "passive"))
      (node (ref "X9") (pin "2") (pinfunction "2_2") (pintype "passive"))
    )
    (net (code "33") (name "Net-(C37-Pad1)") (class "Default")
      (node (ref "C37") (pin "1") (pinfunction "1_1") (pintype "passive"))
      (node (ref "V4") (pin "C") (pinfunction "C_C") (pintype "passive"))
      (node (ref "X10") (pin "2") (pinfunction "2_2") (pintype "passive"))
    )
    (net (code "34") (name "Net-(D1-Y1)") (class "Default")
      (node (ref "D1") (pin "3") (pinfunction "Y1_3") (pintype "bidirectional"))
      (node (ref "R40") (pin "1") (pinfunction "1_1") (pintype "passive"))
    )
    (net (code "35") (name "Net-(D1-Y2)") (class "Default")
      (node (ref "D1") (pin "6") (pinfunction "Y2_6") (pintype "bidirectional"))
      (node (ref "R41") (pin "1") (pinfunction "1_1") (pintype "passive"))
    )
    (net (code "36") (name "Net-(D1-Y3)") (class "Default")
      (node (ref "D1") (pin "8") (pinfunction "Y3_8") (pintype "bidirectional"))
      (node (ref "R42") (pin "1") (pinfunction "1_1") (pintype "passive"))
    )
    (net (code "37") (name "Net-(D2A-BOOT0)") (class "Default")
      (node (ref "D2") (pin "94") (pinfunction "BOOT0_94") (pintype "bidirectional"))
      (node (ref "R27") (pin "2") (pinfunction "2_2") (pintype "passive"))
    )
    (net (code "38") (name "Net-(D2A-PA13{slash}TMS{slash}SWDIO)") (class "Default")
      (node (ref "D2") (pin "72") (pinfunction "PA13/TMS/SWDIO_72") (pintype "bidirectional"))
      (node (ref "R29") (pin "2") (pinfunction "2_2") (pintype "passive"))
    )
    (net (code "39") (name "Net-(D2A-PA14{slash}TCK{slash}SWCLK)") (class "Default")
      (node (ref "D2") (pin "76") (pinfunction "PA14/TCK/SWCLK_76") (pintype "bidirectional"))
      (node (ref "R39") (pin "2") (pinfunction "2_2") (pintype "passive"))
    )
    (net (code "40") (name "Net-(D2A-PB2{slash}BOOT1)") (class "Default")
      (node (ref "D2") (pin "37") (pinfunction "PB2/BOOT1_37") (pintype "bidirectional"))
      (node (ref "R28") (pin "2") (pinfunction "2_2") (pintype "passive"))
    )
    (net (code "41") (name "Net-(D2A-PH0{slash}OSCIN)") (class "Default")
      (node (ref "C32") (pin "1") (pinfunction "1_1") (pintype "passive"))
      (node (ref "D2") (pin "12") (pinfunction "PH0/OSCIN_12") (pintype "bidirectional"))
      (node (ref "G1") (pin "1") (pinfunction "X1_1") (pintype "bidirectional"))
    )
    (net (code "42") (name "Net-(D2A-PH1{slash}OSCOUT)") (class "Default")
      (node (ref "C33") (pin "1") (pinfunction "1_1") (pintype "passive"))
      (node (ref "D2") (pin "13") (pinfunction "PH1/OSCOUT_13") (pintype "bidirectional"))
      (node (ref "G1") (pin "3") (pinfunction "X2_3") (pintype "bidirectional"))
    )
    (net (code "43") (name "Net-(D2A-VCAP1)") (class "Default")
      (node (ref "C18") (pin "1") (pinfunction "1_1") (pintype "passive"))
      (node (ref "D2") (pin "49") (pinfunction "VCAP1_49") (pintype "bidirectional"))
    )
    (net (code "44") (name "Net-(D2A-VCAP2)") (class "Default")
      (node (ref "C17") (pin "1") (pinfunction "1_1") (pintype "passive"))
      (node (ref "D2") (pin "73") (pinfunction "VCAP2_73") (pintype "bidirectional"))
    )
    (net (code "45") (name "Net-(H1-PadC)") (class "Default")
      (node (ref "H1") (pin "C") (pinfunction "C_C") (pintype "passive"))
      (node (ref "R30") (pin "2") (pinfunction "2_2") (pintype "passive"))
    )
    (net (code "46") (name "Net-(H2-PadC)") (class "Default")
      (node (ref "H2") (pin "C") (pinfunction "C_C") (pintype "passive"))
      (node (ref "R31") (pin "2") (pinfunction "2_2") (pintype "passive"))
    )
    (net (code "47") (name "Net-(H3-PadC)") (class "Default")
      (node (ref "H3") (pin "C") (pinfunction "C_C") (pintype "passive"))
      (node (ref "R32") (pin "2") (pinfunction "2_2") (pintype "passive"))
    )
    (net (code "48") (name "Net-(H4-PadC)") (class "Default")
      (node (ref "H4") (pin "C") (pinfunction "C_C") (pintype "passive"))
      (node (ref "R54") (pin "2") (pinfunction "2_2") (pintype "passive"))
    )
    (net (code "49") (name "Net-(N1-ADECAY)") (class "Default")
      (node (ref "N1") (pin "24") (pinfunction "ADECAY_24") (pintype "bidirectional"))
      (node (ref "R4") (pin "2") (pinfunction "2_2") (pintype "passive"))
    )
    (net (code "50") (name "Net-(N1-AISEN)") (class "Default")
      (node (ref "N1") (pin "2") (pinfunction "AISEN_2") (pintype "bidirectional"))
      (node (ref "R5") (pin "2") (pinfunction "2_2") (pintype "passive"))
    )
    (net (code "51") (name "Net-(N1-AOUT1)") (class "Default")
      (node (ref "N1") (pin "1") (pinfunction "AOUT1_1") (pintype "bidirectional"))
      (node (ref "X1") (pin "1") (pinfunction "1_1") (pintype "passive"))
    )
    (net (code "52") (name "Net-(N1-AOUT2)") (class "Default")
      (node (ref "N1") (pin "3") (pinfunction "AOUT2_3") (pintype "bidirectional"))
      (node (ref "X1") (pin "2") (pinfunction "2_2") (pintype "passive"))
    )
    (net (code "53") (name "Net-(N1-AVREF)") (class "Default")
      (node (ref "N1") (pin "19") (pinfunction "AVREF_19") (pintype "bidirectional"))
      (node (ref "N1") (pin "20") (pinfunction "BVREF_20") (pintype "bidirectional"))
      (node (ref "R1") (pin "1") (pinfunction "1_1") (pintype "passive"))
      (node (ref "R2") (pin "2") (pinfunction "2_2") (pintype "passive"))
    )
    (net (code "54") (name "Net-(N1-BDECAY)") (class "Default")
      (node (ref "N1") (pin "23") (pinfunction "BDECAY_23") (pintype "bidirectional"))
      (node (ref "R3") (pin "2") (pinfunction "2_2") (pintype "passive"))
    )
    (net (code "55") (name "Net-(N1-BISEN)") (class "Default")
      (node (ref "N1") (pin "5") (pinfunction "BISEN_5") (pintype "bidirectional"))
      (node (ref "R6") (pin "2") (pinfunction "2_2") (pintype "passive"))
    )
    (net (code "56") (name "Net-(N1-BOUT1)") (class "Default")
      (node (ref "N1") (pin "6") (pinfunction "BOUT1_6") (pintype "bidirectional"))
      (node (ref "X1") (pin "4") (pinfunction "4_4") (pintype "passive"))
    )
    (net (code "57") (name "Net-(N1-BOUT2)") (class "Default")
      (node (ref "N1") (pin "4") (pinfunction "BOUT2_4") (pintype "bidirectional"))
      (node (ref "X1") (pin "3") (pinfunction "3_3") (pintype "passive"))
    )
    (net (code "58") (name "Net-(N1-VCP)") (class "Default")
      (node (ref "C1") (pin "2") (pinfunction "2_2") (pintype "passive"))
      (node (ref "N1") (pin "14") (pinfunction "VCP_14") (pintype "bidirectional"))
    )
    (net (code "59") (name "Net-(N1-VREFO)") (class "Default")
      (node (ref "N1") (pin "21") (pinfunction "VREFO_21") (pintype "bidirectional"))
      (node (ref "R1") (pin "2") (pinfunction "2_2") (pintype "passive"))
    )
    (net (code "60") (name "Net-(N2-ADECAY)") (class "Default")
      (node (ref "N2") (pin "24") (pinfunction "ADECAY_24") (pintype "bidirectional"))
      (node (ref "R10") (pin "2") (pinfunction "2_2") (pintype "passive"))
    )
    (net (code "61") (name "Net-(N2-AISEN)") (class "Default")
      (node (ref "N2") (pin "2") (pinfunction "AISEN_2") (pintype "bidirectional"))
      (node (ref "R11") (pin "2") (pinfunction "2_2") (pintype "passive"))
    )
    (net (code "62") (name "Net-(N2-AOUT1)") (class "Default")
      (node (ref "N2") (pin "1") (pinfunction "AOUT1_1") (pintype "bidirectional"))
      (node (ref "X2") (pin "1") (pinfunction "1_1") (pintype "passive"))
    )
    (net (code "63") (name "Net-(N2-AOUT2)") (class "Default")
      (node (ref "N2") (pin "3") (pinfunction "AOUT2_3") (pintype "bidirectional"))
      (node (ref "X2") (pin "2") (pinfunction "2_2") (pintype "passive"))
    )
    (net (code "64") (name "Net-(N2-AVREF)") (class "Default")
      (node (ref "N2") (pin "19") (pinfunction "AVREF_19") (pintype "bidirectional"))
      (node (ref "N2") (pin "20") (pinfunction "BVREF_20") (pintype "bidirectional"))
      (node (ref "R7") (pin "1") (pinfunction "1_1") (pintype "passive"))
      (node (ref "R8") (pin "2") (pinfunction "2_2") (pintype "passive"))
    )
    (net (code "65") (name "Net-(N2-BDECAY)") (class "Default")
      (node (ref "N2") (pin "23") (pinfunction "BDECAY_23") (pintype "bidirectional"))
      (node (ref "R9") (pin "2") (pinfunction "2_2") (pintype "passive"))
    )
    (net (code "66") (name "Net-(N2-BISEN)") (class "Default")
      (node (ref "N2") (pin "5") (pinfunction "BISEN_5") (pintype "bidirectional"))
      (node (ref "R12") (pin "2") (pinfunction "2_2") (pintype "passive"))
    )
    (net (code "67") (name "Net-(N2-BOUT1)") (class "Default")
      (node (ref "N2") (pin "6") (pinfunction "BOUT1_6") (pintype "bidirectional"))
      (node (ref "X2") (pin "4") (pinfunction "4_4") (pintype "passive"))
    )
    (net (code "68") (name "Net-(N2-BOUT2)") (class "Default")
      (node (ref "N2") (pin "4") (pinfunction "BOUT2_4") (pintype "bidirectional"))
      (node (ref "X2") (pin "3") (pinfunction "3_3") (pintype "passive"))
    )
    (net (code "69") (name "Net-(N2-VCP)") (class "Default")
      (node (ref "C5") (pin "2") (pinfunction "2_2") (pintype "passive"))
      (node (ref "N2") (pin "14") (pinfunction "VCP_14") (pintype "bidirectional"))
    )
    (net (code "70") (name "Net-(N2-VREFO)") (class "Default")
      (node (ref "N2") (pin "21") (pinfunction "VREFO_21") (pintype "bidirectional"))
      (node (ref "R7") (pin "2") (pinfunction "2_2") (pintype "passive"))
    )
    (net (code "71") (name "Net-(N3-ADECAY)") (class "Default")
      (node (ref "N3") (pin "24") (pinfunction "ADECAY_24") (pintype "bidirectional"))
      (node (ref "R16") (pin "2") (pinfunction "2_2") (pintype "passive"))
    )
    (net (code "72") (name "Net-(N3-AISEN)") (class "Default")
      (node (ref "N3") (pin "2") (pinfunction "AISEN_2") (pintype "bidirectional"))
      (node (ref "R17") (pin "2") (pinfunction "2_2") (pintype "passive"))
    )
    (net (code "73") (name "Net-(N3-AOUT1)") (class "Default")
      (node (ref "N3") (pin "1") (pinfunction "AOUT1_1") (pintype "bidirectional"))
      (node (ref "X3") (pin "1") (pinfunction "1_1") (pintype "passive"))
    )
    (net (code "74") (name "Net-(N3-AOUT2)") (class "Default")
      (node (ref "N3") (pin "3") (pinfunction "AOUT2_3") (pintype "bidirectional"))
      (node (ref "X3") (pin "2") (pinfunction "2_2") (pintype "passive"))
    )
    (net (code "75") (name "Net-(N3-AVREF)") (class "Default")
      (node (ref "N3") (pin "19") (pinfunction "AVREF_19") (pintype "bidirectional"))
      (node (ref "N3") (pin "20") (pinfunction "BVREF_20") (pintype "bidirectional"))
      (node (ref "R13") (pin "1") (pinfunction "1_1") (pintype "passive"))
      (node (ref "R14") (pin "2") (pinfunction "2_2") (pintype "passive"))
    )
    (net (code "76") (name "Net-(N3-BDECAY)") (class "Default")
      (node (ref "N3") (pin "23") (pinfunction "BDECAY_23") (pintype "bidirectional"))
      (node (ref "R15") (pin "2") (pinfunction "2_2") (pintype "passive"))
    )
    (net (code "77") (name "Net-(N3-BISEN)") (class "Default")
      (node (ref "N3") (pin "5") (pinfunction "BISEN_5") (pintype "bidirectional"))
      (node (ref "R18") (pin "2") (pinfunction "2_2") (pintype "passive"))
    )
    (net (code "78") (name "Net-(N3-BOUT1)") (class "Default")
      (node (ref "N3") (pin "6") (pinfunction "BOUT1_6") (pintype "bidirectional"))
      (node (ref "X3") (pin "4") (pinfunction "4_4") (pintype "passive"))
    )
    (net (code "79") (name "Net-(N3-BOUT2)") (class "Default")
      (node (ref "N3") (pin "4") (pinfunction "BOUT2_4") (pintype "bidirectional"))
      (node (ref "X3") (pin "3") (pinfunction "3_3") (pintype "passive"))
    )
    (net (code "80") (name "Net-(N3-VCP)") (class "Default")
      (node (ref "C9") (pin "2") (pinfunction "2_2") (pintype "passive"))
      (node (ref "N3") (pin "14") (pinfunction "VCP_14") (pintype "bidirectional"))
    )
    (net (code "81") (name "Net-(N3-VREFO)") (class "Default")
      (node (ref "N3") (pin "21") (pinfunction "VREFO_21") (pintype "bidirectional"))
      (node (ref "R13") (pin "2") (pinfunction "2_2") (pintype "passive"))
    )
    (net (code "82") (name "Net-(N4-ADECAY)") (class "Default")
      (node (ref "N4") (pin "24") (pinfunction "ADECAY_24") (pintype "bidirectional"))
      (node (ref "R22") (pin "2") (pinfunction "2_2") (pintype "passive"))
    )
    (net (code "83") (name "Net-(N4-AISEN)") (class "Default")
      (node (ref "N4") (pin "2") (pinfunction "AISEN_2") (pintype "bidirectional"))
      (node (ref "R23") (pin "2") (pinfunction "2_2") (pintype "passive"))
    )
    (net (code "84") (name "Net-(N4-AOUT1)") (class "Default")
      (node (ref "N4") (pin "1") (pinfunction "AOUT1_1") (pintype "bidirectional"))
      (node (ref "X4") (pin "1") (pinfunction "1_1") (pintype "passive"))
    )
    (net (code "85") (name "Net-(N4-AOUT2)") (class "Default")
      (node (ref "N4") (pin "3") (pinfunction "AOUT2_3") (pintype "bidirectional"))
      (node (ref "X4") (pin "2") (pinfunction "2_2") (pintype "passive"))
    )
    (net (code "86") (name "Net-(N4-AVREF)") (class "Default")
      (node (ref "N4") (pin "19") (pinfunction "AVREF_19") (pintype "bidirectional"))
      (node (ref "N4") (pin "20") (pinfunction "BVREF_20") (pintype "bidirectional"))
      (node (ref "R19") (pin "1") (pinfunction "1_1") (pintype "passive"))
      (node (ref "R20") (pin "2") (pinfunction "2_2") (pintype "passive"))
    )
    (net (code "87") (name "Net-(N4-BDECAY)") (class "Default")
      (node (ref "N4") (pin "23") (pinfunction "BDECAY_23") (pintype "bidirectional"))
      (node (ref "R21") (pin "2") (pinfunction "2_2") (pintype "passive"))
    )
    (net (code "88") (name "Net-(N4-BISEN)") (class "Default")
      (node (ref "N4") (pin "5") (pinfunction "BISEN_5") (pintype "bidirectional"))
      (node (ref "R24") (pin "2") (pinfunction "2_2") (pintype "passive"))
    )
    (net (code "89") (name "Net-(N4-BOUT1)") (class "Default")
      (node (ref "N4") (pin "6") (pinfunction "BOUT1_6") (pintype "bidirectional"))
      (node (ref "X4") (pin "4") (pinfunction "4_4") (pintype "passive"))
    )
    (net (code "90") (name "Net-(N4-BOUT2)") (class "Default")
      (node (ref "N4") (pin "4") (pinfunction "BOUT2_4") (pintype "bidirectional"))
      (node (ref "X4") (pin "3") (pinfunction "3_3") (pintype "passive"))
    )
    (net (code "91") (name "Net-(N4-VCP)") (class "Default")
      (node (ref "C13") (pin "2") (pinfunction "2_2") (pintype "passive"))
      (node (ref "N4") (pin "14") (pinfunction "VCP_14") (pintype "bidirectional"))
    )
    (net (code "92") (name "Net-(N4-VREFO)") (class "Default")
      (node (ref "N4") (pin "21") (pinfunction "VREFO_21") (pintype "bidirectional"))
      (node (ref "R19") (pin "2") (pinfunction "2_2") (pintype "passive"))
    )
    (net (code "93") (name "Net-(N6-BST)") (class "Default")
      (node (ref "C38") (pin "2") (pinfunction "2_2") (pintype "passive"))
      (node (ref "N6") (pin "6") (pinfunction "BST_6") (pintype "bidirectional"))
    )
    (net (code "94") (name "Net-(N6-FB)") (class "Default")
      (node (ref "N6") (pin "4") (pinfunction "FB_4") (pintype "bidirectional"))
      (node (ref "R43") (pin "1") (pinfunction "1_1") (pintype "passive"))
      (node (ref "R44") (pin "2") (pinfunction "2_2") (pintype "passive"))
    )
    (net (code "95") (name "Net-(N6-SW)") (class "Default")
      (node (ref "C38") (pin "1") (pinfunction "1_1") (pintype "passive"))
      (node (ref "L4") (pin "2") (pinfunction "2_2") (pintype "passive"))
      (node (ref "N6") (pin "2") (pinfunction "SW_2") (pintype "bidirectional"))
    )
    (net (code "96") (name "Net-(N7-BST)") (class "Default")
      (node (ref "C42") (pin "2") (pinfunction "2_2") (pintype "passive"))
      (node (ref "N7") (pin "6") (pinfunction "BST_6") (pintype "bidirectional"))
    )
    (net (code "97") (name "Net-(N7-FB)") (class "Default")
      (node (ref "N7") (pin "4") (pinfunction "FB_4") (pintype "bidirectional"))
      (node (ref "R45") (pin "1") (pinfunction "1_1") (pintype "passive"))
      (node (ref "R46") (pin "2") (pinfunction "2_2") (pintype "passive"))
    )
    (net (code "98") (name "Net-(N7-SW)") (class "Default")
      (node (ref "C42") (pin "1") (pinfunction "1_1") (pintype "passive"))
      (node (ref "L1") (pin "2") (pinfunction "2_2") (pintype "passive"))
      (node (ref "N7") (pin "2") (pinfunction "SW_2") (pintype "bidirectional"))
    )
    (net (code "99") (name "Net-(R47-Pad1)") (class "Default")
      (node (ref "R47") (pin "1") (pinfunction "1_1") (pintype "passive"))
      (node (ref "X11") (pin "5") (pinfunction "5_5") (pintype "passive"))
    )
    (net (code "100") (name "Net-(R48-Pad1)") (class "Default")
      (node (ref "R48") (pin "1") (pinfunction "1_1") (pintype "passive"))
      (node (ref "X11") (pin "2") (pinfunction "2_2") (pintype "passive"))
    )
    (net (code "101") (name "Net-(V1-B)") (class "Default")
      (node (ref "R33") (pin "1") (pinfunction "1_1") (pintype "passive"))
      (node (ref "R34") (pin "2") (pinfunction "2_2") (pintype "passive"))
      (node (ref "R35") (pin "1") (pinfunction "1_1") (pintype "passive"))
      (node (ref "V1") (pin "1") (pinfunction "B_1") (pintype "passive"))
    )
    (net (code "102") (name "Net-(V1-E)") (class "Default")
      (node (ref "R37") (pin "2") (pinfunction "2_2") (pintype "passive"))
      (node (ref "V1") (pin "2") (pinfunction "E_2") (pintype "passive"))
    )
    (net (code "103") (name "Net-(X11-Pad4)") (class "Default")
      (node (ref "X11") (pin "4") (pinfunction "4_4") (pintype "passive"))
      (node (ref "X11") (pin "7") (pinfunction "7_7") (pintype "passive"))
    )
    (net (code "104") (name "PSVCC") (class "Default")
      (node (ref "C61") (pin "1") (pinfunction "1_1") (pintype "passive"))
      (node (ref "C62") (pin "1") (pinfunction "1_1") (pintype "passive"))
      (node (ref "L7") (pin "1") (pinfunction "1_1") (pintype "passive"))
      (node (ref "X8") (pin "4") (pinfunction "4_4") (pintype "passive"))
    )
    (net (code "105") (name "PULSE_1") (class "Default")
      (node (ref "D2") (pin "59") (pinfunction "PD12_59") (pintype "bidirectional"))
      (node (ref "N1") (pin "8") (pinfunction "STEP/BENBL_8") (pintype "bidirectional"))
    )
    (net (code "106") (name "PULSE_2") (class "Default")
      (node (ref "D2") (pin "63") (pinfunction "PC6_63") (pintype "bidirectional"))
      (node (ref "N2") (pin "8") (pinfunction "STEP/BENBL_8") (pintype "bidirectional"))
    )
    (net (code "107") (name "PULSE_3") (class "Default")
      (node (ref "D2") (pin "4") (pinfunction "PE5_4") (pintype "bidirectional"))
      (node (ref "N3") (pin "8") (pinfunction "STEP/BENBL_8") (pintype "bidirectional"))
    )
    (net (code "108") (name "PULSE_4") (class "Default")
      (node (ref "D2") (pin "95") (pinfunction "PB8_95") (pintype "bidirectional"))
      (node (ref "N4") (pin "8") (pinfunction "STEP/BENBL_8") (pintype "bidirectional"))
    )
    (net (code "109") (name "RESETL") (class "Default")
      (node (ref "D10") (pin "1") (pinfunction "RESET_1") (pintype "bidirectional"))
      (node (ref "D2") (pin "14") (pinfunction "RSTL_14") (pintype "bidirectional"))
      (node (ref "R25") (pin "1") (pinfunction "1_1") (pintype "passive"))
      (node (ref "X5") (pin "A1") (pinfunction "1_A1") (pintype "passive"))
    )
    (net (code "110") (name "SERVO_1") (class "Default")
      (node (ref "R40") (pin "2") (pinfunction "2_2") (pintype "passive"))
      (node (ref "X7") (pin "1") (pinfunction "1_1") (pintype "passive"))
    )
    (net (code "111") (name "SERVO_2") (class "Default")
      (node (ref "R41") (pin "2") (pinfunction "2_2") (pintype "passive"))
      (node (ref "X9") (pin "1") (pinfunction "1_1") (pintype "passive"))
    )
    (net (code "112") (name "SERVO_3") (class "Default")
      (node (ref "R42") (pin "2") (pinfunction "2_2") (pintype "passive"))
      (node (ref "X10") (pin "1") (pinfunction "1_1") (pintype "passive"))
    )
    (net (code "113") (name "SERVO_PWM_1") (class "Default")
      (node (ref "D1") (pin "2") (pinfunction "A1_2") (pintype "bidirectional"))
      (node (ref "D2") (pin "31") (pinfunction "PA6_31") (pintype "bidirectional"))
    )
    (net (code "114") (name "SERVO_PWM_2") (class "Default")
      (node (ref "D1") (pin "5") (pinfunction "A2_5") (pintype "bidirectional"))
      (node (ref "D2") (pin "32") (pinfunction "PA7_32") (pintype "bidirectional"))
    )
    (net (code "115") (name "SERVO_PWM_3") (class "Default")
      (node (ref "D1") (pin "9") (pinfunction "A3_9") (pintype "bidirectional"))
      (node (ref "D2") (pin "35") (pinfunction "PB0_35") (pintype "bidirectional"))
    )
    (net (code "116") (name "SLEEP_N") (class "Default")
      (node (ref "D2") (pin "86") (pinfunction "PD5_86") (pintype "bidirectional"))
      (node (ref "N1") (pin "22") (pinfunction "NSLEEP_22") (pintype "bidirectional"))
      (node (ref "N2") (pin "22") (pinfunction "NSLEEP_22") (pintype "bidirectional"))
      (node (ref "N3") (pin "22") (pinfunction "NSLEEP_22") (pintype "bidirectional"))
      (node (ref "N4") (pin "22") (pinfunction "NSLEEP_22") (pintype "bidirectional"))
    )
    (net (code "117") (name "SPI1CLK") (class "Default")
      (node (ref "D2") (pin "89") (pinfunction "PB3/TDO_89") (pintype "bidirectional"))
      (node (ref "R88") (pin "2") (pinfunction "2_2") (pintype "passive"))
    )
    (net (code "118") (name "SPI1MISO") (class "Default")
      (node (ref "D2") (pin "90") (pinfunction "PB4/TRSTL_90") (pintype "bidirectional"))
      (node (ref "R38") (pin "2") (pinfunction "2_2") (pintype "passive"))
    )
    (net (code "119") (name "SPI1MOSI") (class "Default")
      (node (ref "D2") (pin "91") (pinfunction "PB5_91") (pintype "bidirectional"))
      (node (ref "R86") (pin "2") (pinfunction "2_2") (pintype "passive"))
    )
    (net (code "120") (name "SPI_CS_PS2_N") (class "Default")
      (node (ref "D2") (pin "24") (pinfunction "PA1_24") (pintype "bidirectional"))
      (node (ref "R87") (pin "2") (pinfunction "2_2") (pintype "passive"))
    )
    (net (code "121") (name "SWCLK") (class "Default")
      (node (ref "R39") (pin "1") (pinfunction "1_1") (pintype "passive"))
      (node (ref "X5") (pin "A3") (pinfunction "3_A3") (pintype "passive"))
    )
    (net (code "122") (name "SWDIO") (class "Default")
      (node (ref "R29") (pin "1") (pinfunction "1_1") (pintype "passive"))
      (node (ref "X5") (pin "A2") (pinfunction "2_A2") (pintype "passive"))
    )
    (net (code "123") (name "USART1RX") (class "Default")
      (node (ref "D2") (pin "69") (pinfunction "PA10_69") (pintype "bidirectional"))
      (node (ref "R47") (pin "2") (pinfunction "2_2") (pintype "passive"))
    )
    (net (code "124") (name "USART1TX") (class "Default")
      (node (ref "D2") (pin "68") (pinfunction "PA9_68") (pintype "bidirectional"))
      (node (ref "R48") (pin "2") (pinfunction "2_2") (pintype "passive"))
    )
    (net (code "125") (name "USART1TXE") (class "Default")
      (node (ref "D2") (pin "62") (pinfunction "PD15_62") (pintype "bidirectional"))
    )
    (net (code "126") (name "USART3RX") (class "Default")
      (node (ref "D2") (pin "56") (pinfunction "PD9_56") (pintype "bidirectional"))
      (node (ref "X5") (pin "A4") (pinfunction "4_A4") (pintype "passive"))
    )
    (net (code "127") (name "USART3TX") (class "Default")
      (node (ref "D2") (pin "55") (pinfunction "PD8_55") (pintype "bidirectional"))
      (node (ref "X5") (pin "A5") (pinfunction "5_A5") (pintype "passive"))
    )
    (net (code "128") (name "USBRENUM") (class "Default")
      (node (ref "D2") (pin "54") (pinfunction "PB15_54") (pintype "bidirectional"))
      (node (ref "R33") (pin "2") (pinfunction "2_2") (pintype "passive"))
    )
    (net (code "129") (name "USB_DM") (class "Default")
      (node (ref "D2") (pin "70") (pinfunction "PA11_70") (pintype "bidirectional"))
      (node (ref "V26") (pin "4") (pinfunction "D_4") (pintype "bidirectional"))
      (node (ref "X12") (pin "2") (pinfunction "2_2") (pintype "passive"))
    )
    (net (code "130") (name "USB_DP") (class "Default")
      (node (ref "D2") (pin "71") (pinfunction "PA12_71") (pintype "bidirectional"))
      (node (ref "R37") (pin "1") (pinfunction "1_1") (pintype "passive"))
      (node (ref "V26") (pin "3") (pinfunction "C_3") (pintype "bidirectional"))
      (node (ref "X12") (pin "3") (pinfunction "3_3") (pintype "passive"))
    )
    (net (code "131") (name "VDDA") (class "Default")
      (node (ref "C19") (pin "1") (pinfunction "1_1") (pintype "passive"))
      (node (ref "C20") (pin "1") (pinfunction "1_1") (pintype "passive"))
      (node (ref "D2") (pin "22") (pinfunction "VDDA_22") (pintype "bidirectional"))
      (node (ref "L2") (pin "1") (pinfunction "1_1") (pintype "passive"))
    )
    (net (code "132") (name "VDDAREF") (class "Default")
      (node (ref "C54") (pin "1") (pinfunction "1_1") (pintype "passive"))
      (node (ref "C55") (pin "1") (pinfunction "1_1") (pintype "passive"))
      (node (ref "L3") (pin "1") (pinfunction "1_1") (pintype "passive"))
      (node (ref "N5") (pin "1") (pinfunction "VDD_1") (pintype "bidirectional"))
      (node (ref "N5") (pin "3") (pinfunction "SHDNL_3") (pintype "power_in"))
    )
    (net (code "133") (name "VINT_1") (class "Default")
      (node (ref "C2") (pin "1") (pinfunction "1_1") (pintype "passive"))
      (node (ref "N1") (pin "11") (pinfunction "M1_11") (pintype "bidirectional"))
      (node (ref "N1") (pin "12") (pinfunction "CONFIG_12") (pintype "bidirectional"))
      (node (ref "N1") (pin "17") (pinfunction "VINT_17") (pintype "bidirectional"))
    )
    (net (code "134") (name "VINT_2") (class "Default")
      (node (ref "C6") (pin "1") (pinfunction "1_1") (pintype "passive"))
      (node (ref "N2") (pin "11") (pinfunction "M1_11") (pintype "bidirectional"))
      (node (ref "N2") (pin "12") (pinfunction "CONFIG_12") (pintype "bidirectional"))
      (node (ref "N2") (pin "17") (pinfunction "VINT_17") (pintype "bidirectional"))
    )
    (net (code "135") (name "VINT_3") (class "Default")
      (node (ref "C10") (pin "1") (pinfunction "1_1") (pintype "passive"))
      (node (ref "N3") (pin "11") (pinfunction "M1_11") (pintype "bidirectional"))
      (node (ref "N3") (pin "12") (pinfunction "CONFIG_12") (pintype "bidirectional"))
      (node (ref "N3") (pin "17") (pinfunction "VINT_17") (pintype "bidirectional"))
    )
    (net (code "136") (name "VINT_4") (class "Default")
      (node (ref "C14") (pin "1") (pinfunction "1_1") (pintype "passive"))
      (node (ref "N4") (pin "11") (pinfunction "M1_11") (pintype "bidirectional"))
      (node (ref "N4") (pin "12") (pinfunction "CONFIG_12") (pintype "bidirectional"))
      (node (ref "N4") (pin "17") (pinfunction "VINT_17") (pintype "bidirectional"))
    )
    (net (code "137") (name "VREF25") (class "Default")
      (node (ref "D2") (pin "21") (pinfunction "VREF+_21") (pintype "bidirectional"))
      (node (ref "N5") (pin "7") (pinfunction "OUT_7") (pintype "bidirectional"))
      (node (ref "N5") (pin "8") (pinfunction "FEEDBACK_8") (pintype "input"))
      (node (ref "R26") (pin "2") (pinfunction "2_2") (pintype "passive"))
    )
    (net (code "138") (name "VUSB") (class "Default")
      (node (ref "R35") (pin "2") (pinfunction "2_2") (pintype "passive"))
      (node (ref "V26") (pin "5") (pinfunction "VCC_5") (pintype "bidirectional"))
      (node (ref "X12") (pin "1") (pinfunction "1_1") (pintype "passive"))
    )
    (net (code "139") (name "unconnected-(D1-Y4-Pad11)") (class "Default")
      (node (ref "D1") (pin "11") (pinfunction "Y4_11") (pintype "bidirectional"))
    )
    (net (code "140") (name "unconnected-(D2A-PA15{slash}TDI-Pad77)") (class "Default")
      (node (ref "D2") (pin "77") (pinfunction "PA15/TDI_77") (pintype "bidirectional"))
    )
    (net (code "141") (name "unconnected-(D2A-PC14{slash}OSC32IN-Pad8)") (class "Default")
      (node (ref "D2") (pin "8") (pinfunction "PC14/OSC32IN_8") (pintype "bidirectional"))
    )
    (net (code "142") (name "unconnected-(D2A-PC15{slash}OSC32OUT-Pad9)") (class "Default")
      (node (ref "D2") (pin "9") (pinfunction "PC15/OSC32OUT_9") (pintype "bidirectional"))
    )
    (net (code "143") (name "unconnected-(D2B-PA2-Pad25)") (class "Default")
      (node (ref "D2") (pin "25") (pinfunction "PA2_25") (pintype "bidirectional"))
    )
    (net (code "144") (name "unconnected-(D2B-PA3-Pad26)") (class "Default")
      (node (ref "D2") (pin "26") (pinfunction "PA3_26") (pintype "bidirectional"))
    )
    (net (code "145") (name "unconnected-(D2B-PA4-Pad29)") (class "Default")
      (node (ref "D2") (pin "29") (pinfunction "PA4_29") (pintype "bidirectional"))
    )
    (net (code "146") (name "unconnected-(D2B-PA5-Pad30)") (class "Default")
      (node (ref "D2") (pin "30") (pinfunction "PA5_30") (pintype "bidirectional"))
    )
    (net (code "147") (name "unconnected-(D2B-PA8-Pad67)") (class "Default")
      (node (ref "D2") (pin "67") (pinfunction "PA8_67") (pintype "bidirectional"))
    )
    (net (code "148") (name "unconnected-(D2B-PB1-Pad36)") (class "Default")
      (node (ref "D2") (pin "36") (pinfunction "PB1_36") (pintype "bidirectional"))
    )
    (net (code "149") (name "unconnected-(D2B-PB9-Pad96)") (class "Default")
      (node (ref "D2") (pin "96") (pinfunction "PB9_96") (pintype "bidirectional"))
    )
    (net (code "150") (name "unconnected-(D2B-PB10-Pad47)") (class "Default")
      (node (ref "D2") (pin "47") (pinfunction "PB10_47") (pintype "bidirectional"))
    )
    (net (code "151") (name "unconnected-(D2B-PB11-Pad48)") (class "Default")
      (node (ref "D2") (pin "48") (pinfunction "PB11_48") (pintype "bidirectional"))
    )
    (net (code "152") (name "unconnected-(D2B-PB12-Pad51)") (class "Default")
      (node (ref "D2") (pin "51") (pinfunction "PB12_51") (pintype "bidirectional"))
    )
    (net (code "153") (name "unconnected-(D2B-PB13-Pad52)") (class "Default")
      (node (ref "D2") (pin "52") (pinfunction "PB13_52") (pintype "bidirectional"))
    )
    (net (code "154") (name "unconnected-(D2B-PB14-Pad53)") (class "Default")
      (node (ref "D2") (pin "53") (pinfunction "PB14_53") (pintype "bidirectional"))
    )
    (net (code "155") (name "unconnected-(D2B-PC0-Pad15)") (class "Default")
      (node (ref "D2") (pin "15") (pinfunction "PC0_15") (pintype "bidirectional"))
    )
    (net (code "156") (name "unconnected-(D2B-PC1-Pad16)") (class "Default")
      (node (ref "D2") (pin "16") (pinfunction "PC1_16") (pintype "bidirectional"))
    )
    (net (code "157") (name "unconnected-(D2B-PC2-Pad17)") (class "Default")
      (node (ref "D2") (pin "17") (pinfunction "PC2_17") (pintype "bidirectional"))
    )
    (net (code "158") (name "unconnected-(D2B-PC3-Pad18)") (class "Default")
      (node (ref "D2") (pin "18") (pinfunction "PC3_18") (pintype "bidirectional"))
    )
    (net (code "159") (name "unconnected-(D2B-PC4-Pad33)") (class "Default")
      (node (ref "D2") (pin "33") (pinfunction "PC4_33") (pintype "bidirectional"))
    )
    (net (code "160") (name "unconnected-(D2B-PC5-Pad34)") (class "Default")
      (node (ref "D2") (pin "34") (pinfunction "PC5_34") (pintype "bidirectional"))
    )
    (net (code "161") (name "unconnected-(D2B-PC7-Pad64)") (class "Default")
      (node (ref "D2") (pin "64") (pinfunction "PC7_64") (pintype "bidirectional"))
    )
    (net (code "162") (name "unconnected-(D2B-PC8-Pad65)") (class "Default")
      (node (ref "D2") (pin "65") (pinfunction "PC8_65") (pintype "bidirectional"))
    )
    (net (code "163") (name "unconnected-(D2B-PC9-Pad66)") (class "Default")
      (node (ref "D2") (pin "66") (pinfunction "PC9_66") (pintype "bidirectional"))
    )
    (net (code "164") (name "unconnected-(D2B-PD7-Pad88)") (class "Default")
      (node (ref "D2") (pin "88") (pinfunction "PD7_88") (pintype "bidirectional"))
    )
    (net (code "165") (name "unconnected-(D2B-PD10-Pad57)") (class "Default")
      (node (ref "D2") (pin "57") (pinfunction "PD10_57") (pintype "bidirectional"))
    )
    (net (code "166") (name "unconnected-(D2B-PD11-Pad58)") (class "Default")
      (node (ref "D2") (pin "58") (pinfunction "PD11_58") (pintype "bidirectional"))
    )
    (net (code "167") (name "unconnected-(D2B-PD13-Pad60)") (class "Default")
      (node (ref "D2") (pin "60") (pinfunction "PD13_60") (pintype "bidirectional"))
    )
    (net (code "168") (name "unconnected-(D2B-PD14-Pad61)") (class "Default")
      (node (ref "D2") (pin "61") (pinfunction "PD14_61") (pintype "bidirectional"))
    )
    (net (code "169") (name "unconnected-(D2C-PE0-Pad97)") (class "Default")
      (node (ref "D2") (pin "97") (pinfunction "PE0_97") (pintype "bidirectional"))
    )
    (net (code "170") (name "unconnected-(D2C-PE1-Pad98)") (class "Default")
      (node (ref "D2") (pin "98") (pinfunction "PE1_98") (pintype "bidirectional"))
    )
    (net (code "171") (name "unconnected-(D2C-PE6-Pad5)") (class "Default")
      (node (ref "D2") (pin "5") (pinfunction "PE6_5") (pintype "bidirectional"))
    )
    (net (code "172") (name "unconnected-(D2C-PE7-Pad38)") (class "Default")
      (node (ref "D2") (pin "38") (pinfunction "PE7_38") (pintype "bidirectional"))
    )
    (net (code "173") (name "unconnected-(D2C-PE9-Pad40)") (class "Default")
      (node (ref "D2") (pin "40") (pinfunction "PE9_40") (pintype "bidirectional"))
    )
    (net (code "174") (name "unconnected-(D2C-PE13-Pad44)") (class "Default")
      (node (ref "D2") (pin "44") (pinfunction "PE13_44") (pintype "bidirectional"))
    )
    (net (code "175") (name "unconnected-(D2C-PE14-Pad45)") (class "Default")
      (node (ref "D2") (pin "45") (pinfunction "PE14_45") (pintype "bidirectional"))
    )
    (net (code "176") (name "unconnected-(D2C-PE15-Pad46)") (class "Default")
      (node (ref "D2") (pin "46") (pinfunction "PE15_46") (pintype "bidirectional"))
    )
    (net (code "177") (name "unconnected-(V26-A-Pad1)") (class "Default")
      (node (ref "V26") (pin "1") (pinfunction "A_1") (pintype "bidirectional"))
    )
    (net (code "178") (name "unconnected-(V26-B-Pad6)") (class "Default")
      (node (ref "V26") (pin "6") (pinfunction "B_6") (pintype "bidirectional"))
    )
    (net (code "179") (name "unconnected-(X5B-1-PadB1)") (class "Default")
      (node (ref "X5") (pin "B1") (pinfunction "1_B1") (pintype "passive"))
    )
    (net (code "180") (name "unconnected-(X11-Pad1)") (class "Default")
      (node (ref "X11") (pin "1") (pinfunction "1_1") (pintype "passive"))
    )
    (net (code "181") (name "unconnected-(X12-Pad4)") (class "Default")
      (node (ref "X12") (pin "4") (pinfunction "4_4") (pintype "passive"))
    )
  )
)
